# washberry.net
KiCad netlist of a schematic drawn in EAGLE
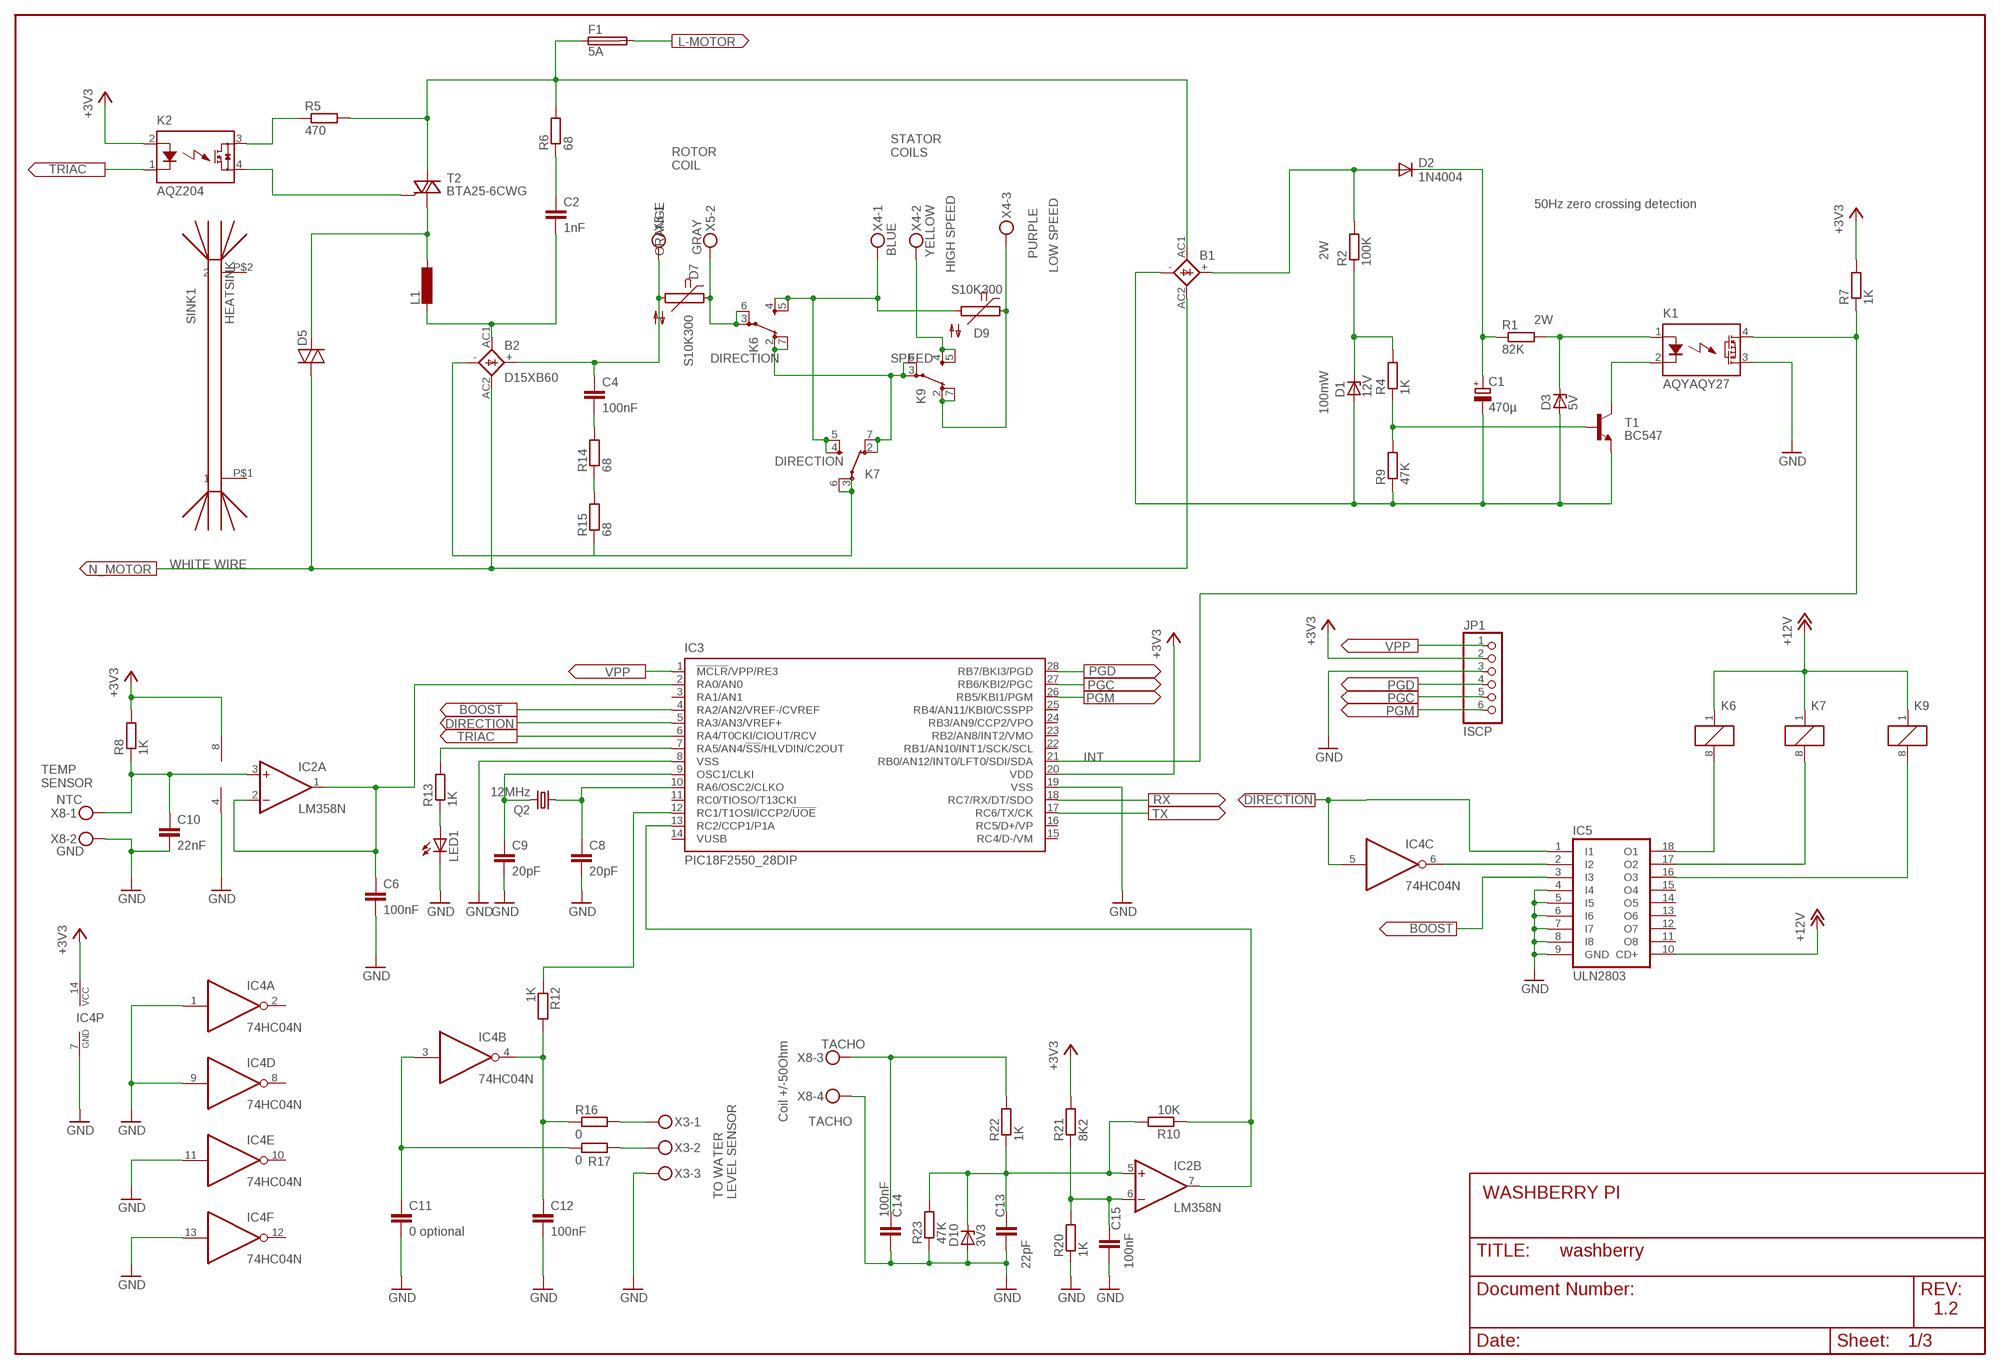
[diagram p0: schematic, sheet 1]
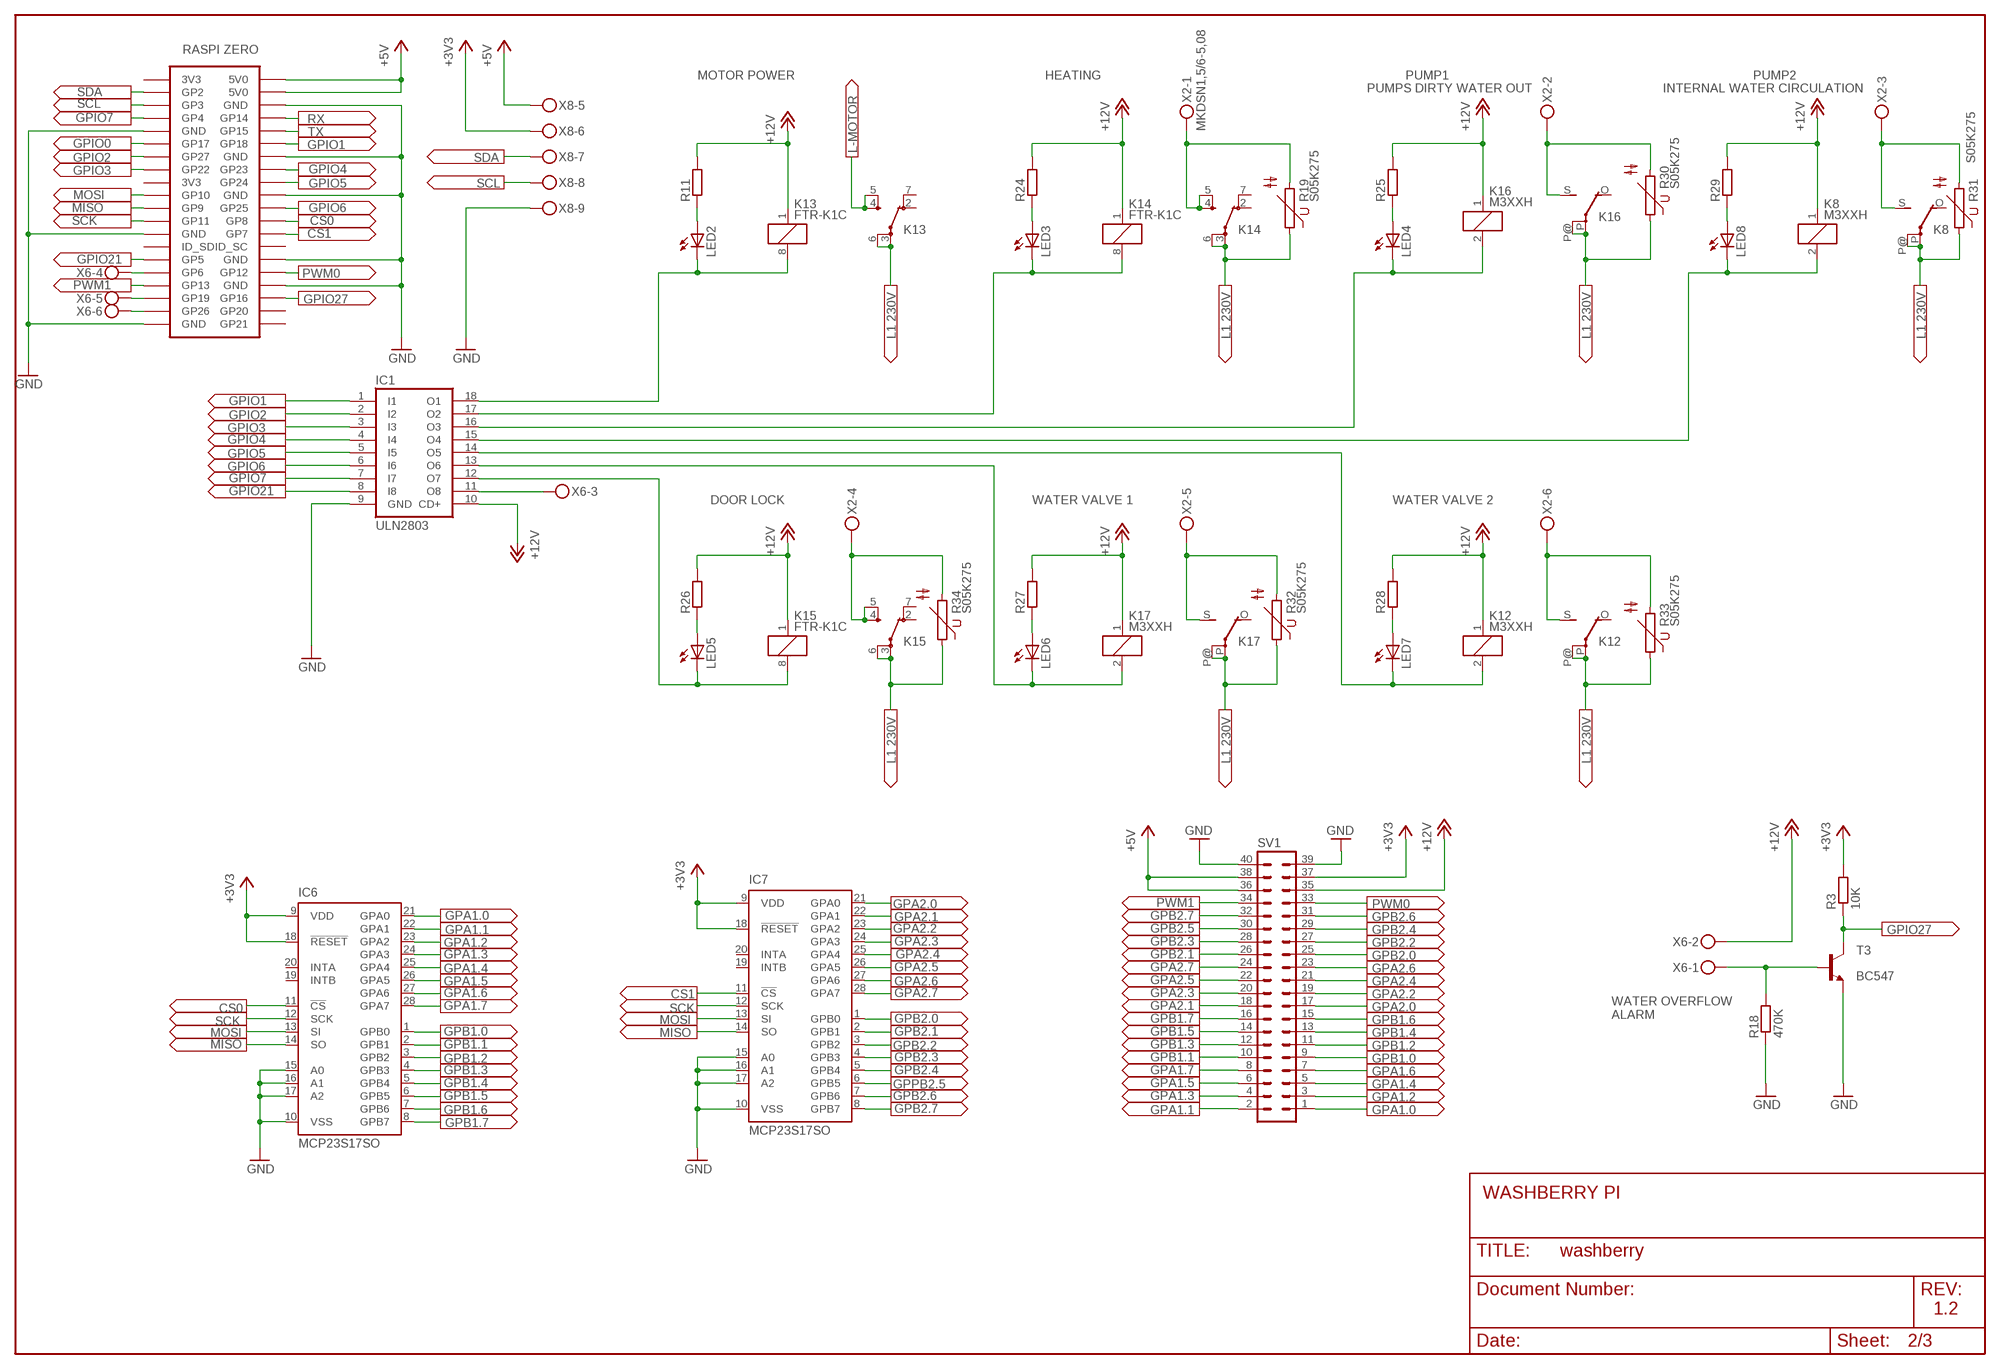
[diagram p1: schematic, sheet 2]
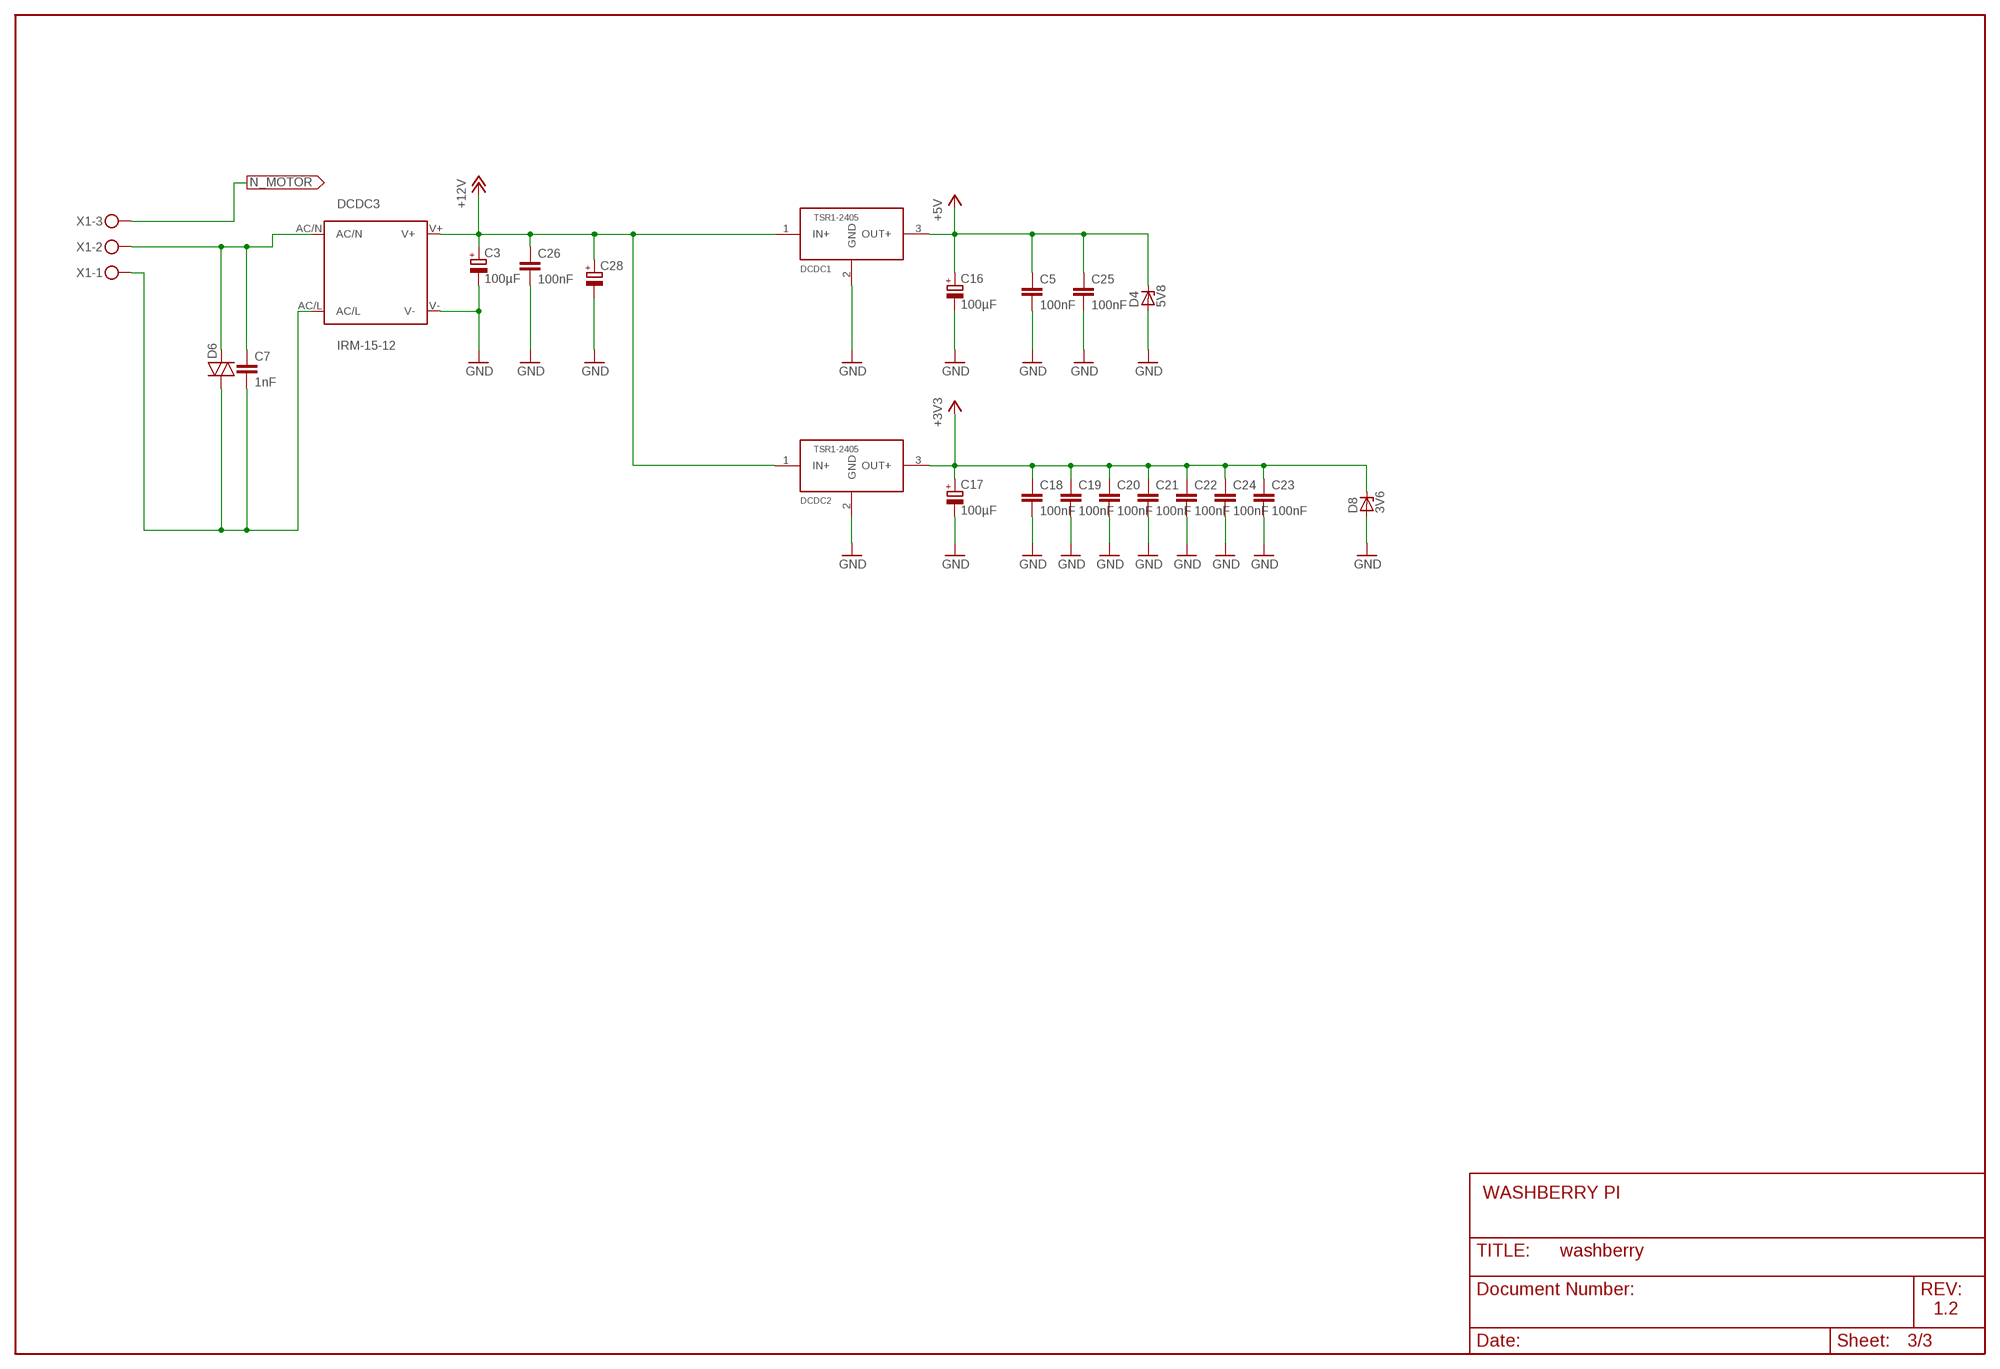
[diagram p2: schematic, sheet 3]

(export (version "E")
  (design (tool "Eeschema 10.0.6"))
  (components
    (comp (ref "IC1")
      (value "ULN2803")
      (footprint "eagle-import:DIL18")
      (libsource (lib "eagle-import") (part "ULN2803A"))
    )
    (comp (ref "IC6")
      (value "MCP23S17SO")
      (footprint "eagle-import:SO28W")
      (fields (field (name "MF") "MICROCHIP") (field (name "MPN") "MCP23S17-E/SO"))
      (libsource (lib "eagle-import") (part "MCP23S17SO"))
    )
    (comp (ref "IC7")
      (value "MCP23S17SO")
      (footprint "eagle-import:SO28W")
      (fields (field (name "MF") "MICROCHIP") (field (name "MPN") "MCP23S17-E/SO"))
      (libsource (lib "eagle-import") (part "MCP23S17SO"))
    )
    (comp (ref "K8")
      (value "M3XXH")
      (footprint "eagle-import:M3XXH")
      (libsource (lib "eagle-import") (part "M3XXH"))
    )
    (comp (ref "K12")
      (value "M3XXH")
      (footprint "eagle-import:M3XXH")
      (libsource (lib "eagle-import") (part "M3XXH"))
    )
    (comp (ref "K13")
      (value "FTR-K1C")
      (footprint "eagle-import:FTR-K1C")
      (libsource (lib "eagle-import") (part "FTR-K1C"))
    )
    (comp (ref "K14")
      (value "FTR-K1C")
      (footprint "eagle-import:FTR-K1C")
      (libsource (lib "eagle-import") (part "FTR-K1C"))
    )
    (comp (ref "K15")
      (value "FTR-K1C")
      (footprint "eagle-import:FTR-K1C")
      (libsource (lib "eagle-import") (part "FTR-K1C"))
    )
    (comp (ref "K16")
      (value "M3XXH")
      (footprint "eagle-import:M3XXH")
      (libsource (lib "eagle-import") (part "M3XXH"))
    )
    (comp (ref "K17")
      (value "M3XXH")
      (footprint "eagle-import:M3XXH")
      (libsource (lib "eagle-import") (part "M3XXH"))
    )
    (comp (ref "LED2")
      (value "LEDSML0805")
      (footprint "eagle-import:SML0805")
      (libsource (lib "eagle-import") (part "LEDSML0805"))
    )
    (comp (ref "LED3")
      (value "LEDSML0805")
      (footprint "eagle-import:SML0805")
      (libsource (lib "eagle-import") (part "LEDSML0805"))
    )
    (comp (ref "LED4")
      (value "LEDSML0805")
      (footprint "eagle-import:SML0805")
      (libsource (lib "eagle-import") (part "LEDSML0805"))
    )
    (comp (ref "LED5")
      (value "LEDSML0805")
      (footprint "eagle-import:SML0805")
      (libsource (lib "eagle-import") (part "LEDSML0805"))
    )
    (comp (ref "LED6")
      (value "LEDSML0805")
      (footprint "eagle-import:SML0805")
      (libsource (lib "eagle-import") (part "LEDSML0805"))
    )
    (comp (ref "LED7")
      (value "LEDSML0805")
      (footprint "eagle-import:SML0805")
      (libsource (lib "eagle-import") (part "LEDSML0805"))
    )
    (comp (ref "LED8")
      (value "LEDSML0805")
      (footprint "eagle-import:SML0805")
      (libsource (lib "eagle-import") (part "LEDSML0805"))
    )
    (comp (ref "R3")
      (value "10K")
      (footprint "eagle-import:0207_2V")
      (libsource (lib "eagle-import") (part "R-EU_0207/2V"))
    )
    (comp (ref "R11")
      (value "R-EU_R0805")
      (footprint "eagle-import:R0805")
      (libsource (lib "eagle-import") (part "R-EU_R0805"))
    )
    (comp (ref "R18")
      (value "470K")
      (footprint "eagle-import:0207_2V")
      (libsource (lib "eagle-import") (part "R-EU_0207/2V"))
    )
    (comp (ref "R19")
      (value "S05K275")
      (footprint "eagle-import:S05K275")
      (libsource (lib "eagle-import") (part "S05K275"))
    )
    (comp (ref "R24")
      (value "R-EU_R0805")
      (footprint "eagle-import:R0805")
      (libsource (lib "eagle-import") (part "R-EU_R0805"))
    )
    (comp (ref "R25")
      (value "R-EU_R0805")
      (footprint "eagle-import:R0805")
      (libsource (lib "eagle-import") (part "R-EU_R0805"))
    )
    (comp (ref "R26")
      (value "R-EU_R0805")
      (footprint "eagle-import:R0805")
      (libsource (lib "eagle-import") (part "R-EU_R0805"))
    )
    (comp (ref "R27")
      (value "R-EU_R0805")
      (footprint "eagle-import:R0805")
      (libsource (lib "eagle-import") (part "R-EU_R0805"))
    )
    (comp (ref "R28")
      (value "R-EU_R0805")
      (footprint "eagle-import:R0805")
      (libsource (lib "eagle-import") (part "R-EU_R0805"))
    )
    (comp (ref "R29")
      (value "R-EU_R0805")
      (footprint "eagle-import:R0805")
      (libsource (lib "eagle-import") (part "R-EU_R0805"))
    )
    (comp (ref "R30")
      (value "S05K275")
      (footprint "eagle-import:S05K275")
      (libsource (lib "eagle-import") (part "S05K275"))
    )
    (comp (ref "R31")
      (value "S05K275")
      (footprint "eagle-import:S05K275")
      (libsource (lib "eagle-import") (part "S05K275"))
    )
    (comp (ref "R32")
      (value "S05K275")
      (footprint "eagle-import:S05K275")
      (libsource (lib "eagle-import") (part "S05K275"))
    )
    (comp (ref "R33")
      (value "S05K275")
      (footprint "eagle-import:S05K275")
      (libsource (lib "eagle-import") (part "S05K275"))
    )
    (comp (ref "R34")
      (value "S05K275")
      (footprint "eagle-import:S05K275")
      (libsource (lib "eagle-import") (part "S05K275"))
    )
    (comp (ref "SV1")
      (value "ML40")
      (footprint "eagle-import:ML40")
      (libsource (lib "eagle-import") (part "ML40"))
    )
    (comp (ref "T3")
      (value "BC547")
      (footprint "eagle-import:TO92")
      (libsource (lib "eagle-import") (part "BC547"))
    )
    (comp (ref "U$3")
      (value "ZERO")
      (footprint "eagle-import:ZERO_NO_DIMENSION")
      (libsource (lib "eagle-import") (part "ZERO"))
    )
    (comp (ref "X2")
      (value "MKDSN1,5/6-5,08")
      (footprint "eagle-import:MKDSN1,5_6-5,08")
      (fields (field (name "MPN") "SMKDSN1,5/6-5,08"))
      (libsource (lib "eagle-import") (part "MKDSN1,5/6-5,08"))
    )
    (comp (ref "X6")
      (value "MKDSN1,5/6-5,08")
      (footprint "eagle-import:MKDSN1,5_6-5,08")
      (fields (field (name "MPN") "SMKDSN1,5/6-5,08"))
      (libsource (lib "eagle-import") (part "MKDSN1,5/6-5,08"))
    )
    (comp (ref "X8")
      (value "MKDSN1,5/9-5,08")
      (footprint "eagle-import:MKDSN1,5_9-5,08")
      (fields (field (name "MPN") "SMKDSN1,5/9-5,08"))
      (libsource (lib "eagle-import") (part "MKDSN1,5/9-5,08"))
    )
    (comp (ref "B1")
      (value "2KBB")
      (footprint "eagle-import:2KBB")
      (libsource (lib "eagle-import") (part "2KBB"))
    )
    (comp (ref "B2")
      (value "D15XB60")
      (footprint "eagle-import:5S")
      (libsource (lib "eagle-import") (part "D15XB60"))
    )
    (comp (ref "C1")
      (value "470µ")
      (footprint "eagle-import:E5-13")
      (libsource (lib "eagle-import") (part "CPOL-EUE5-13"))
    )
    (comp (ref "C2")
      (value "1nF")
      (footprint "eagle-import:C150-054X183")
      (libsource (lib "eagle-import") (part "C-EU150-054X183"))
    )
    (comp (ref "C4")
      (value "100nF")
      (footprint "eagle-import:C150-054X183")
      (libsource (lib "eagle-import") (part "C-EU150-054X183"))
    )
    (comp (ref "C6")
      (value "100nF")
      (footprint "eagle-import:C025-024X044")
      (libsource (lib "eagle-import") (part "C-EU025-024X044"))
    )
    (comp (ref "C8")
      (value "20pF")
      (footprint "eagle-import:C025-024X044")
      (libsource (lib "eagle-import") (part "C-EU025-024X044"))
    )
    (comp (ref "C9")
      (value "20pF")
      (footprint "eagle-import:C025-024X044")
      (libsource (lib "eagle-import") (part "C-EU025-024X044"))
    )
    (comp (ref "C10")
      (value "22nF")
      (footprint "eagle-import:C025-024X044")
      (libsource (lib "eagle-import") (part "C-EU025-024X044"))
    )
    (comp (ref "C11")
      (value "0 optional")
      (footprint "eagle-import:C025-024X044")
      (libsource (lib "eagle-import") (part "C-EU025-024X044"))
    )
    (comp (ref "C12")
      (value "100nF")
      (footprint "eagle-import:C025-024X044")
      (libsource (lib "eagle-import") (part "C-EU025-024X044"))
    )
    (comp (ref "C13")
      (value "22pF")
      (footprint "eagle-import:C025-024X044")
      (libsource (lib "eagle-import") (part "C-EU025-024X044"))
    )
    (comp (ref "C14")
      (value "100nF")
      (footprint "eagle-import:C025-024X044")
      (libsource (lib "eagle-import") (part "C-EU025-024X044"))
    )
    (comp (ref "C15")
      (value "100nF")
      (footprint "eagle-import:C025-024X044")
      (libsource (lib "eagle-import") (part "C-EU025-024X044"))
    )
    (comp (ref "D1")
      (value "12V")
      (footprint "eagle-import:DO34Z7")
      (libsource (lib "eagle-import") (part "ZENER-DIODEDO34-7"))
    )
    (comp (ref "D2")
      (value "1N4004")
      (footprint "eagle-import:DO41-10")
      (libsource (lib "eagle-import") (part "1N4004"))
    )
    (comp (ref "D3")
      (value "5V")
      (footprint "eagle-import:DO34Z7")
      (libsource (lib "eagle-import") (part "ZENER-DIODEDO34-7"))
    )
    (comp (ref "D5")
      (value "DIAC-DO35-10")
      (footprint "eagle-import:DO35-10")
      (libsource (lib "eagle-import") (part "DIAC-DO35-10"))
    )
    (comp (ref "D7")
      (value "S10K300")
      (footprint "eagle-import:S10K300")
      (libsource (lib "eagle-import") (part "S10K300"))
    )
    (comp (ref "D9")
      (value "S10K300")
      (footprint "eagle-import:S10K300")
      (libsource (lib "eagle-import") (part "S10K300"))
    )
    (comp (ref "D10")
      (value "3V3")
      (footprint "eagle-import:DO34Z7")
      (libsource (lib "eagle-import") (part "ZENER-DIODEDO34-7"))
    )
    (comp (ref "F1")
      (value "5A")
      (footprint "eagle-import:GSH15")
      (fields (field (name "MPN") "64900001039"))
      (libsource (lib "eagle-import") (part "GSH15"))
    )
    (comp (ref "IC2")
      (value "LM358N")
      (footprint "eagle-import:DIL08")
      (libsource (lib "eagle-import") (part "LM358N"))
    )
    (comp (ref "IC3")
      (value "PIC18F2550_28DIP")
      (footprint "eagle-import:DIL28-3")
      (fields (field (name "MF") "MICROCHIP") (field (name "MPN") "PIC18F2550-I/SP"))
      (libsource (lib "eagle-import") (part "PIC18F2_28DIP550"))
    )
    (comp (ref "IC4")
      (value "74HC04N")
      (footprint "eagle-import:DIL14")
      (libsource (lib "eagle-import") (part "7404NHC"))
    )
    (comp (ref "IC5")
      (value "ULN2803")
      (footprint "eagle-import:DIL18")
      (libsource (lib "eagle-import") (part "ULN2803A"))
    )
    (comp (ref "JP1")
      (value "ISCP")
      (footprint "eagle-import:1X06")
      (libsource (lib "eagle-import") (part "PINHD-1X6"))
    )
    (comp (ref "K1")
      (value "AQYAQY27")
      (footprint "eagle-import:AQY27")
      (libsource (lib "eagle-import") (part "AQYAQY27"))
    )
    (comp (ref "K2")
      (value "AQZ204")
      (footprint "eagle-import:AQZ-SIL04")
      (libsource (lib "eagle-import") (part "AQZ204"))
    )
    (comp (ref "K6")
      (value "FTR-K1C")
      (footprint "eagle-import:FTR-K1C")
      (libsource (lib "eagle-import") (part "FTR-K1C"))
    )
    (comp (ref "K7")
      (value "FTR-K1C")
      (footprint "eagle-import:FTR-K1C")
      (libsource (lib "eagle-import") (part "FTR-K1C"))
    )
    (comp (ref "K9")
      (value "FTR-K1C")
      (footprint "eagle-import:FTR-K1C")
      (libsource (lib "eagle-import") (part "FTR-K1C"))
    )
    (comp (ref "L1")
      (value "L-EUTJ5-U1")
      (footprint "eagle-import:TJ5-U1")
      (libsource (lib "eagle-import") (part "L-EUTJ5-U1"))
    )
    (comp (ref "LED1")
      (value "LEDCHIPLED_0805")
      (footprint "eagle-import:CHIPLED_0805")
      (libsource (lib "eagle-import") (part "LEDCHIPLED_0805"))
    )
    (comp (ref "Q2")
      (value "12MHz")
      (footprint "eagle-import:HC49_S")
      (libsource (lib "eagle-import") (part "CRYSTALHC49S"))
    )
    (comp (ref "R1")
      (value "82K")
      (footprint "eagle-import:0617_17")
      (libsource (lib "eagle-import") (part "R-EU_0617/17"))
    )
    (comp (ref "R2")
      (value "100K")
      (footprint "eagle-import:0617_17")
      (libsource (lib "eagle-import") (part "R-EU_0617/17"))
    )
    (comp (ref "R4")
      (value "1K")
      (footprint "eagle-import:0411V")
      (libsource (lib "eagle-import") (part "R-EU_0411/3V"))
    )
    (comp (ref "R5")
      (value "470")
      (footprint "eagle-import:P0613_15")
      (libsource (lib "eagle-import") (part "R-EU_0613/15"))
    )
    (comp (ref "R6")
      (value "68")
      (footprint "eagle-import:P0613_15")
      (libsource (lib "eagle-import") (part "R-EU_0613/15"))
    )
    (comp (ref "R7")
      (value "1K")
      (footprint "eagle-import:0411V")
      (libsource (lib "eagle-import") (part "R-EU_0411/3V"))
    )
    (comp (ref "R8")
      (value "1K")
      (footprint "eagle-import:0411V")
      (libsource (lib "eagle-import") (part "R-EU_0411/3V"))
    )
    (comp (ref "R9")
      (value "47K")
      (footprint "eagle-import:0411V")
      (libsource (lib "eagle-import") (part "R-EU_0411/3V"))
    )
    (comp (ref "R10")
      (value "10K")
      (footprint "eagle-import:0411V")
      (libsource (lib "eagle-import") (part "R-EU_0411/3V"))
    )
    (comp (ref "R12")
      (value "1K")
      (footprint "eagle-import:0411V")
      (libsource (lib "eagle-import") (part "R-EU_0411/3V"))
    )
    (comp (ref "R13")
      (value "1K")
      (footprint "eagle-import:R0805")
      (libsource (lib "eagle-import") (part "R-EU_R0805"))
    )
    (comp (ref "R14")
      (value "68")
      (footprint "eagle-import:0617_17")
      (libsource (lib "eagle-import") (part "R-EU_0617/17"))
    )
    (comp (ref "R15")
      (value "68")
      (footprint "eagle-import:0617_17")
      (libsource (lib "eagle-import") (part "R-EU_0617/17"))
    )
    (comp (ref "R16")
      (value "0")
      (footprint "eagle-import:0411V")
      (libsource (lib "eagle-import") (part "R-EU_0411/3V"))
    )
    (comp (ref "R17")
      (value "0")
      (footprint "eagle-import:0411V")
      (libsource (lib "eagle-import") (part "R-EU_0411/3V"))
    )
    (comp (ref "R20")
      (value "1K")
      (footprint "eagle-import:0411V")
      (libsource (lib "eagle-import") (part "R-EU_0411/3V"))
    )
    (comp (ref "R21")
      (value "8K2")
      (footprint "eagle-import:0411V")
      (libsource (lib "eagle-import") (part "R-EU_0411/3V"))
    )
    (comp (ref "R22")
      (value "1K")
      (footprint "eagle-import:0411V")
      (libsource (lib "eagle-import") (part "R-EU_0411/3V"))
    )
    (comp (ref "R23")
      (value "47K")
      (footprint "eagle-import:0411V")
      (libsource (lib "eagle-import") (part "R-EU_0411/3V"))
    )
    (comp (ref "SINK1")
      (value "HEATSINK")
      (footprint "eagle-import:W_HEATSINK")
      (libsource (lib "eagle-import") (part "W_HEATSINK"))
    )
    (comp (ref "T1")
      (value "BC547")
      (footprint "eagle-import:TO92")
      (libsource (lib "eagle-import") (part "BC547"))
    )
    (comp (ref "T2")
      (value "BTA25-6CWG")
      (footprint "eagle-import:TO220BV")
      (libsource (lib "eagle-import") (part "BT138-V"))
    )
    (comp (ref "X3")
      (value "MKDSN1,5/3-5,08")
      (footprint "eagle-import:MKDSN1,5_3-5,08")
      (fields (field (name "MPN") "SMKDSN1,5/3-5,08"))
      (libsource (lib "eagle-import") (part "MKDSN1,5/3-5,08"))
    )
    (comp (ref "X4")
      (value "MKDSN1,5/3-5,08")
      (footprint "eagle-import:MKDSN1,5_3-5,08")
      (fields (field (name "MPN") "SMKDSN1,5/3-5,08"))
      (libsource (lib "eagle-import") (part "MKDSN1,5/3-5,08"))
    )
    (comp (ref "X5")
      (value "MKDSN1,5/2-5,08")
      (footprint "eagle-import:MKDSN1,5_2-5,08")
      (fields (field (name "MPN") "MKDSN 1,5/2-5.08"))
      (libsource (lib "eagle-import") (part "MKDSN1,5/2-5,08"))
    )
    (comp (ref "C3")
      (value "100µF")
      (footprint "eagle-import:E3,5-8")
      (libsource (lib "eagle-import") (part "CPOL-EUE3.5-8"))
    )
    (comp (ref "C5")
      (value "100nF")
      (footprint "eagle-import:C025-024X044")
      (libsource (lib "eagle-import") (part "C-EU025-024X044"))
    )
    (comp (ref "C7")
      (value "1nF")
      (footprint "eagle-import:C150-091X182")
      (libsource (lib "eagle-import") (part "C-EU150-091X182"))
    )
    (comp (ref "C16")
      (value "100µF")
      (footprint "eagle-import:E3,5-8")
      (libsource (lib "eagle-import") (part "CPOL-EUE3.5-8"))
    )
    (comp (ref "C17")
      (value "100µF")
      (footprint "eagle-import:E2-5")
      (libsource (lib "eagle-import") (part "CPOL-EUE2-5"))
    )
    (comp (ref "C18")
      (value "100nF")
      (footprint "eagle-import:C025-024X044")
      (libsource (lib "eagle-import") (part "C-EU025-024X044"))
    )
    (comp (ref "C19")
      (value "100nF")
      (footprint "eagle-import:C025-024X044")
      (libsource (lib "eagle-import") (part "C-EU025-024X044"))
    )
    (comp (ref "C20")
      (value "100nF")
      (footprint "eagle-import:C025-024X044")
      (libsource (lib "eagle-import") (part "C-EU025-024X044"))
    )
    (comp (ref "C21")
      (value "100nF")
      (footprint "eagle-import:C025-024X044")
      (libsource (lib "eagle-import") (part "C-EU025-024X044"))
    )
    (comp (ref "C22")
      (value "100nF")
      (footprint "eagle-import:C025-024X044")
      (libsource (lib "eagle-import") (part "C-EU025-024X044"))
    )
    (comp (ref "C23")
      (value "100nF")
      (footprint "eagle-import:C025-024X044")
      (libsource (lib "eagle-import") (part "C-EU025-024X044"))
    )
    (comp (ref "C24")
      (value "100nF")
      (footprint "eagle-import:C025-024X044")
      (libsource (lib "eagle-import") (part "C-EU025-024X044"))
    )
    (comp (ref "C25")
      (value "100nF")
      (footprint "eagle-import:C025-024X044")
      (libsource (lib "eagle-import") (part "C-EU025-024X044"))
    )
    (comp (ref "C26")
      (value "100nF")
      (footprint "eagle-import:C025-024X044")
      (libsource (lib "eagle-import") (part "C-EU025-024X044"))
    )
    (comp (ref "C28")
      (value "CPOL-EUE2-5")
      (footprint "eagle-import:E2-5")
      (libsource (lib "eagle-import") (part "CPOL-EUE2-5"))
    )
    (comp (ref "D4")
      (value "5V8")
      (footprint "eagle-import:DO34Z7")
      (libsource (lib "eagle-import") (part "ZENER-DIODEDO34-7"))
    )
    (comp (ref "D6")
      (value "DIAC-DO35-10")
      (footprint "eagle-import:DO35-10")
      (libsource (lib "eagle-import") (part "DIAC-DO35-10"))
    )
    (comp (ref "D8")
      (value "3V6")
      (footprint "eagle-import:DO34Z7")
      (libsource (lib "eagle-import") (part "ZENER-DIODEDO34-7"))
    )
    (comp (ref "DCDC1")
      (value "TSR1-2405")
      (footprint "eagle-import:SIPTO220")
      (libsource (lib "eagle-import") (part "TSR1-24XX"))
    )
    (comp (ref "DCDC2")
      (value "TSR1-2405")
      (footprint "eagle-import:SIPTO220")
      (libsource (lib "eagle-import") (part "TSR1-24XX"))
    )
    (comp (ref "DCDC3")
      (value "IRM-15-12")
      (footprint "eagle-import:IRM_15_20")
      (libsource (lib "eagle-import") (part "IRM_15/20IRM_15/20"))
    )
    (comp (ref "X1")
      (value "MKDSN1,5/3-5,08")
      (footprint "eagle-import:MKDSN1,5_3-5,08")
      (fields (field (name "MPN") "SMKDSN1,5/3-5,08"))
      (libsource (lib "eagle-import") (part "MKDSN1,5/3-5,08"))
    )
  )
  (nets
    (net (code "1") (name "+3V3") (class "Default")
      (node (ref "C17") (pin "+") (pinfunction "+_+") (pintype "passive"))
      (node (ref "C18") (pin "1") (pinfunction "1_1") (pintype "passive"))
      (node (ref "C19") (pin "1") (pinfunction "1_1") (pintype "passive"))
      (node (ref "C20") (pin "1") (pinfunction "1_1") (pintype "passive"))
      (node (ref "C21") (pin "1") (pinfunction "1_1") (pintype "passive"))
      (node (ref "C22") (pin "1") (pinfunction "1_1") (pintype "passive"))
      (node (ref "C23") (pin "1") (pinfunction "1_1") (pintype "passive"))
      (node (ref "C24") (pin "1") (pinfunction "1_1") (pintype "passive"))
      (node (ref "D8") (pin "C") (pinfunction "C_C") (pintype "passive"))
      (node (ref "DCDC2") (pin "3") (pinfunction "OUT+_3") (pintype "output"))
      (node (ref "IC2") (pin "8") (pinfunction "V+_8") (pintype "power_in"))
      (node (ref "IC3") (pin "20") (pinfunction "VDD_20") (pintype "power_in"))
      (node (ref "IC4") (pin "14") (pinfunction "VCC_14") (pintype "power_in"))
      (node (ref "IC6") (pin "18") (pinfunction "~{RESET}_18") (pintype "input"))
      (node (ref "IC6") (pin "9") (pinfunction "VDD_9") (pintype "power_in"))
      (node (ref "IC7") (pin "18") (pinfunction "~{RESET}_18") (pintype "input"))
      (node (ref "IC7") (pin "9") (pinfunction "VDD_9") (pintype "power_in"))
      (node (ref "JP1") (pin "2") (pinfunction "2_2") (pintype "passive"))
      (node (ref "K2") (pin "2") (pinfunction "A_2") (pintype "passive"))
      (node (ref "R21") (pin "2") (pinfunction "2_2") (pintype "passive"))
      (node (ref "R3") (pin "2") (pinfunction "2_2") (pintype "passive"))
      (node (ref "R7") (pin "2") (pinfunction "2_2") (pintype "passive"))
      (node (ref "R8") (pin "2") (pinfunction "2_2") (pintype "passive"))
      (node (ref "SV1") (pin "37") (pinfunction "37_37") (pintype "passive"))
      (node (ref "X8") (pin "6") (pinfunction "KL_6") (pintype "passive"))
    )
    (net (code "2") (name "+5V") (class "Default")
      (node (ref "C16") (pin "+") (pinfunction "+_+") (pintype "passive"))
      (node (ref "C25") (pin "1") (pinfunction "1_1") (pintype "passive"))
      (node (ref "C5") (pin "1") (pinfunction "1_1") (pintype "passive"))
      (node (ref "D4") (pin "C") (pinfunction "C_C") (pintype "passive"))
      (node (ref "DCDC1") (pin "3") (pinfunction "OUT+_3") (pintype "output"))
      (node (ref "SV1") (pin "36") (pinfunction "36_36") (pintype "passive"))
      (node (ref "SV1") (pin "38") (pinfunction "38_38") (pintype "passive"))
      (node (ref "U$3") (pin "2") (pinfunction "5V0_2") (pintype "bidirectional"))
      (node (ref "U$3") (pin "4") (pinfunction "5V0_4") (pintype "bidirectional"))
      (node (ref "X8") (pin "5") (pinfunction "KL_5") (pintype "passive"))
    )
    (net (code "3") (name "+12V") (class "Default")
      (node (ref "C26") (pin "1") (pinfunction "1_1") (pintype "passive"))
      (node (ref "C28") (pin "+") (pinfunction "+_+") (pintype "passive"))
      (node (ref "C3") (pin "+") (pinfunction "+_+") (pintype "passive"))
      (node (ref "DCDC1") (pin "1") (pinfunction "IN+_1") (pintype "bidirectional"))
      (node (ref "DCDC2") (pin "1") (pinfunction "IN+_1") (pintype "bidirectional"))
      (node (ref "DCDC3") (pin "V+") (pinfunction "V+_V+") (pintype "output"))
      (node (ref "IC1") (pin "10") (pinfunction "CD+_10") (pintype "passive"))
      (node (ref "IC5") (pin "10") (pinfunction "CD+_10") (pintype "passive"))
      (node (ref "K12") (pin "1") (pinfunction "1_1") (pintype "passive"))
      (node (ref "K13") (pin "1") (pinfunction "1_1") (pintype "passive"))
      (node (ref "K14") (pin "1") (pinfunction "1_1") (pintype "passive"))
      (node (ref "K15") (pin "1") (pinfunction "1_1") (pintype "passive"))
      (node (ref "K16") (pin "1") (pinfunction "1_1") (pintype "passive"))
      (node (ref "K17") (pin "1") (pinfunction "1_1") (pintype "passive"))
      (node (ref "K6") (pin "1") (pinfunction "1_1") (pintype "passive"))
      (node (ref "K7") (pin "1") (pinfunction "1_1") (pintype "passive"))
      (node (ref "K8") (pin "1") (pinfunction "1_1") (pintype "passive"))
      (node (ref "K9") (pin "1") (pinfunction "1_1") (pintype "passive"))
      (node (ref "R11") (pin "2") (pinfunction "2_2") (pintype "passive"))
      (node (ref "R24") (pin "2") (pinfunction "2_2") (pintype "passive"))
      (node (ref "R25") (pin "2") (pinfunction "2_2") (pintype "passive"))
      (node (ref "R26") (pin "2") (pinfunction "2_2") (pintype "passive"))
      (node (ref "R27") (pin "2") (pinfunction "2_2") (pintype "passive"))
      (node (ref "R28") (pin "2") (pinfunction "2_2") (pintype "passive"))
      (node (ref "R29") (pin "2") (pinfunction "2_2") (pintype "passive"))
      (node (ref "SV1") (pin "35") (pinfunction "35_35") (pintype "passive"))
      (node (ref "X6") (pin "2") (pinfunction "KL_2") (pintype "passive"))
    )
    (net (code "4") (name "BOOST") (class "Default")
      (node (ref "IC3") (pin "4") (pinfunction "RA2/AN2/VREF-/CVREF_4") (pintype "bidirectional"))
      (node (ref "IC5") (pin "3") (pinfunction "I3_3") (pintype "input"))
    )
    (net (code "5") (name "CS0") (class "Default")
      (node (ref "IC6") (pin "11") (pinfunction "~{CS}_11") (pintype "input"))
      (node (ref "U$3") (pin "24") (pinfunction "GP8_24") (pintype "bidirectional"))
    )
    (net (code "6") (name "CS1") (class "Default")
      (node (ref "IC7") (pin "11") (pinfunction "~{CS}_11") (pintype "input"))
      (node (ref "U$3") (pin "26") (pinfunction "GP7_26") (pintype "bidirectional"))
    )
    (net (code "7") (name "DIRECTION") (class "Default")
      (node (ref "IC3") (pin "5") (pinfunction "RA3/AN3/VREF+_5") (pintype "bidirectional"))
      (node (ref "IC4") (pin "5") (pinfunction "I_5") (pintype "input"))
      (node (ref "IC5") (pin "1") (pinfunction "I1_1") (pintype "input"))
    )
    (net (code "8") (name "GND") (class "Default")
      (node (ref "C10") (pin "2") (pinfunction "2_2") (pintype "passive"))
      (node (ref "C11") (pin "2") (pinfunction "2_2") (pintype "passive"))
      (node (ref "C12") (pin "2") (pinfunction "2_2") (pintype "passive"))
      (node (ref "C13") (pin "2") (pinfunction "2_2") (pintype "passive"))
      (node (ref "C14") (pin "2") (pinfunction "2_2") (pintype "passive"))
      (node (ref "C15") (pin "2") (pinfunction "2_2") (pintype "passive"))
      (node (ref "C16") (pin "-") (pinfunction "-_-") (pintype "passive"))
      (node (ref "C17") (pin "-") (pinfunction "-_-") (pintype "passive"))
      (node (ref "C18") (pin "2") (pinfunction "2_2") (pintype "passive"))
      (node (ref "C19") (pin "2") (pinfunction "2_2") (pintype "passive"))
      (node (ref "C20") (pin "2") (pinfunction "2_2") (pintype "passive"))
      (node (ref "C21") (pin "2") (pinfunction "2_2") (pintype "passive"))
      (node (ref "C22") (pin "2") (pinfunction "2_2") (pintype "passive"))
      (node (ref "C23") (pin "2") (pinfunction "2_2") (pintype "passive"))
      (node (ref "C24") (pin "2") (pinfunction "2_2") (pintype "passive"))
      (node (ref "C25") (pin "2") (pinfunction "2_2") (pintype "passive"))
      (node (ref "C26") (pin "2") (pinfunction "2_2") (pintype "passive"))
      (node (ref "C28") (pin "-") (pinfunction "-_-") (pintype "passive"))
      (node (ref "C3") (pin "-") (pinfunction "-_-") (pintype "passive"))
      (node (ref "C5") (pin "2") (pinfunction "2_2") (pintype "passive"))
      (node (ref "C6") (pin "2") (pinfunction "2_2") (pintype "passive"))
      (node (ref "C8") (pin "2") (pinfunction "2_2") (pintype "passive"))
      (node (ref "C9") (pin "2") (pinfunction "2_2") (pintype "passive"))
      (node (ref "D10") (pin "A") (pinfunction "A_A") (pintype "passive"))
      (node (ref "D4") (pin "A") (pinfunction "A_A") (pintype "passive"))
      (node (ref "D8") (pin "A") (pinfunction "A_A") (pintype "passive"))
      (node (ref "DCDC1") (pin "2") (pinfunction "GND_2") (pintype "bidirectional"))
      (node (ref "DCDC2") (pin "2") (pinfunction "GND_2") (pintype "bidirectional"))
      (node (ref "DCDC3") (pin "V-") (pinfunction "V-_V-") (pintype "output"))
      (node (ref "IC1") (pin "9") (pinfunction "GND_9") (pintype "power_in"))
      (node (ref "IC2") (pin "4") (pinfunction "V-_4") (pintype "power_in"))
      (node (ref "IC3") (pin "19") (pinfunction "VSS_19") (pintype "power_in"))
      (node (ref "IC3") (pin "8") (pinfunction "VSS_8") (pintype "power_in"))
      (node (ref "IC4") (pin "1") (pinfunction "I_1") (pintype "input"))
      (node (ref "IC4") (pin "11") (pinfunction "I_11") (pintype "input"))
      (node (ref "IC4") (pin "13") (pinfunction "I_13") (pintype "input"))
      (node (ref "IC4") (pin "7") (pinfunction "GND_7") (pintype "power_in"))
      (node (ref "IC4") (pin "9") (pinfunction "I_9") (pintype "input"))
      (node (ref "IC5") (pin "4") (pinfunction "I4_4") (pintype "input"))
      (node (ref "IC5") (pin "5") (pinfunction "I5_5") (pintype "input"))
      (node (ref "IC5") (pin "6") (pinfunction "I6_6") (pintype "input"))
      (node (ref "IC5") (pin "7") (pinfunction "I7_7") (pintype "input"))
      (node (ref "IC5") (pin "8") (pinfunction "I8_8") (pintype "input"))
      (node (ref "IC5") (pin "9") (pinfunction "GND_9") (pintype "power_in"))
      (node (ref "IC6") (pin "10") (pinfunction "VSS_10") (pintype "power_in"))
      (node (ref "IC6") (pin "15") (pinfunction "A0_15") (pintype "input"))
      (node (ref "IC6") (pin "16") (pinfunction "A1_16") (pintype "input"))
      (node (ref "IC6") (pin "17") (pinfunction "A2_17") (pintype "input"))
      (node (ref "IC7") (pin "10") (pinfunction "VSS_10") (pintype "power_in"))
      (node (ref "IC7") (pin "15") (pinfunction "A0_15") (pintype "input"))
      (node (ref "IC7") (pin "16") (pinfunction "A1_16") (pintype "input"))
      (node (ref "IC7") (pin "17") (pinfunction "A2_17") (pintype "input"))
      (node (ref "JP1") (pin "3") (pinfunction "3_3") (pintype "passive"))
      (node (ref "K1") (pin "3") (pinfunction "DS2_3") (pintype "passive"))
      (node (ref "LED1") (pin "C") (pinfunction "C_C") (pintype "passive"))
      (node (ref "R18") (pin "1") (pinfunction "1_1") (pintype "passive"))
      (node (ref "R20") (pin "1") (pinfunction "1_1") (pintype "passive"))
      (node (ref "R23") (pin "1") (pinfunction "1_1") (pintype "passive"))
      (node (ref "SV1") (pin "39") (pinfunction "39_39") (pintype "passive"))
      (node (ref "SV1") (pin "40") (pinfunction "40_40") (pintype "passive"))
      (node (ref "T3") (pin "1") (pinfunction "E_1") (pintype "passive"))
      (node (ref "U$3") (pin "14") (pinfunction "GND_14") (pintype "bidirectional"))
      (node (ref "U$3") (pin "20") (pinfunction "GND_20") (pintype "bidirectional"))
      (node (ref "U$3") (pin "25") (pinfunction "GND_25") (pintype "bidirectional"))
      (node (ref "U$3") (pin "30") (pinfunction "GND_30") (pintype "bidirectional"))
      (node (ref "U$3") (pin "34") (pinfunction "GND_34") (pintype "bidirectional"))
      (node (ref "U$3") (pin "39") (pinfunction "GND_39") (pintype "bidirectional"))
      (node (ref "U$3") (pin "6") (pinfunction "GND_6") (pintype "bidirectional"))
      (node (ref "U$3") (pin "9") (pinfunction "GND_9") (pintype "bidirectional"))
      (node (ref "X3") (pin "3") (pinfunction "KL_3") (pintype "passive"))
      (node (ref "X8") (pin "2") (pinfunction "KL_2") (pintype "passive"))
      (node (ref "X8") (pin "4") (pinfunction "KL_4") (pintype "passive"))
      (node (ref "X8") (pin "9") (pinfunction "KL_9") (pintype "passive"))
    )
    (net (code "9") (name "GPA1.0") (class "Default")
      (node (ref "IC6") (pin "21") (pinfunction "GPA0_21") (pintype "bidirectional"))
      (node (ref "SV1") (pin "1") (pinfunction "1_1") (pintype "passive"))
    )
    (net (code "10") (name "GPA1.1") (class "Default")
      (node (ref "IC6") (pin "22") (pinfunction "GPA1_22") (pintype "bidirectional"))
      (node (ref "SV1") (pin "2") (pinfunction "2_2") (pintype "passive"))
    )
    (net (code "11") (name "GPA1.2") (class "Default")
      (node (ref "IC6") (pin "23") (pinfunction "GPA2_23") (pintype "bidirectional"))
      (node (ref "SV1") (pin "3") (pinfunction "3_3") (pintype "passive"))
    )
    (net (code "12") (name "GPA1.3") (class "Default")
      (node (ref "IC6") (pin "24") (pinfunction "GPA3_24") (pintype "bidirectional"))
      (node (ref "SV1") (pin "4") (pinfunction "4_4") (pintype "passive"))
    )
    (net (code "13") (name "GPA1.4") (class "Default")
      (node (ref "IC6") (pin "25") (pinfunction "GPA4_25") (pintype "bidirectional"))
      (node (ref "SV1") (pin "5") (pinfunction "5_5") (pintype "passive"))
    )
    (net (code "14") (name "GPA1.5") (class "Default")
      (node (ref "IC6") (pin "26") (pinfunction "GPA5_26") (pintype "bidirectional"))
      (node (ref "SV1") (pin "6") (pinfunction "6_6") (pintype "passive"))
    )
    (net (code "15") (name "GPA1.6") (class "Default")
      (node (ref "IC6") (pin "27") (pinfunction "GPA6_27") (pintype "bidirectional"))
      (node (ref "SV1") (pin "7") (pinfunction "7_7") (pintype "passive"))
    )
    (net (code "16") (name "GPA1.7") (class "Default")
      (node (ref "IC6") (pin "28") (pinfunction "GPA7_28") (pintype "bidirectional"))
      (node (ref "SV1") (pin "8") (pinfunction "8_8") (pintype "passive"))
    )
    (net (code "17") (name "GPA2.0") (class "Default")
      (node (ref "IC7") (pin "21") (pinfunction "GPA0_21") (pintype "bidirectional"))
      (node (ref "SV1") (pin "17") (pinfunction "17_17") (pintype "passive"))
    )
    (net (code "18") (name "GPA2.1") (class "Default")
      (node (ref "IC7") (pin "22") (pinfunction "GPA1_22") (pintype "bidirectional"))
      (node (ref "SV1") (pin "18") (pinfunction "18_18") (pintype "passive"))
    )
    (net (code "19") (name "GPA2.2") (class "Default")
      (node (ref "IC7") (pin "23") (pinfunction "GPA2_23") (pintype "bidirectional"))
      (node (ref "SV1") (pin "19") (pinfunction "19_19") (pintype "passive"))
    )
    (net (code "20") (name "GPA2.3") (class "Default")
      (node (ref "IC7") (pin "24") (pinfunction "GPA3_24") (pintype "bidirectional"))
      (node (ref "SV1") (pin "20") (pinfunction "20_20") (pintype "passive"))
    )
    (net (code "21") (name "GPA2.4") (class "Default")
      (node (ref "IC7") (pin "25") (pinfunction "GPA4_25") (pintype "bidirectional"))
      (node (ref "SV1") (pin "21") (pinfunction "21_21") (pintype "passive"))
    )
    (net (code "22") (name "GPA2.5") (class "Default")
      (node (ref "IC7") (pin "26") (pinfunction "GPA5_26") (pintype "bidirectional"))
      (node (ref "SV1") (pin "22") (pinfunction "22_22") (pintype "passive"))
    )
    (net (code "23") (name "GPA2.6") (class "Default")
      (node (ref "IC7") (pin "27") (pinfunction "GPA6_27") (pintype "bidirectional"))
      (node (ref "SV1") (pin "23") (pinfunction "23_23") (pintype "passive"))
    )
    (net (code "24") (name "GPA2.7") (class "Default")
      (node (ref "IC7") (pin "28") (pinfunction "GPA7_28") (pintype "bidirectional"))
      (node (ref "SV1") (pin "24") (pinfunction "24_24") (pintype "passive"))
    )
    (net (code "25") (name "GPB1.0") (class "Default")
      (node (ref "IC6") (pin "1") (pinfunction "GPB0_1") (pintype "bidirectional"))
      (node (ref "SV1") (pin "9") (pinfunction "9_9") (pintype "passive"))
    )
    (net (code "26") (name "GPB1.1") (class "Default")
      (node (ref "IC6") (pin "2") (pinfunction "GPB1_2") (pintype "bidirectional"))
      (node (ref "SV1") (pin "10") (pinfunction "10_10") (pintype "passive"))
    )
    (net (code "27") (name "GPB1.2") (class "Default")
      (node (ref "IC6") (pin "3") (pinfunction "GPB2_3") (pintype "bidirectional"))
      (node (ref "SV1") (pin "11") (pinfunction "11_11") (pintype "passive"))
    )
    (net (code "28") (name "GPB1.3") (class "Default")
      (node (ref "IC6") (pin "4") (pinfunction "GPB3_4") (pintype "bidirectional"))
      (node (ref "SV1") (pin "12") (pinfunction "12_12") (pintype "passive"))
    )
    (net (code "29") (name "GPB1.4") (class "Default")
      (node (ref "IC6") (pin "5") (pinfunction "GPB4_5") (pintype "bidirectional"))
      (node (ref "SV1") (pin "13") (pinfunction "13_13") (pintype "passive"))
    )
    (net (code "30") (name "GPB1.5") (class "Default")
      (node (ref "IC6") (pin "6") (pinfunction "GPB5_6") (pintype "bidirectional"))
      (node (ref "SV1") (pin "14") (pinfunction "14_14") (pintype "passive"))
    )
    (net (code "31") (name "GPB1.6") (class "Default")
      (node (ref "IC6") (pin "7") (pinfunction "GPB6_7") (pintype "bidirectional"))
      (node (ref "SV1") (pin "15") (pinfunction "15_15") (pintype "passive"))
    )
    (net (code "32") (name "GPB1.7") (class "Default")
      (node (ref "IC6") (pin "8") (pinfunction "GPB7_8") (pintype "bidirectional"))
      (node (ref "SV1") (pin "16") (pinfunction "16_16") (pintype "passive"))
    )
    (net (code "33") (name "GPB2.0") (class "Default")
      (node (ref "IC7") (pin "1") (pinfunction "GPB0_1") (pintype "bidirectional"))
      (node (ref "SV1") (pin "25") (pinfunction "25_25") (pintype "passive"))
    )
    (net (code "34") (name "GPB2.1") (class "Default")
      (node (ref "IC7") (pin "2") (pinfunction "GPB1_2") (pintype "bidirectional"))
      (node (ref "SV1") (pin "26") (pinfunction "26_26") (pintype "passive"))
    )
    (net (code "35") (name "GPB2.2") (class "Default")
      (node (ref "IC7") (pin "3") (pinfunction "GPB2_3") (pintype "bidirectional"))
      (node (ref "SV1") (pin "27") (pinfunction "27_27") (pintype "passive"))
    )
    (net (code "36") (name "GPB2.3") (class "Default")
      (node (ref "IC7") (pin "4") (pinfunction "GPB3_4") (pintype "bidirectional"))
      (node (ref "SV1") (pin "28") (pinfunction "28_28") (pintype "passive"))
    )
    (net (code "37") (name "GPB2.4") (class "Default")
      (node (ref "IC7") (pin "5") (pinfunction "GPB4_5") (pintype "bidirectional"))
      (node (ref "SV1") (pin "29") (pinfunction "29_29") (pintype "passive"))
    )
    (net (code "38") (name "GPB2.5") (class "Default")
      (node (ref "SV1") (pin "30") (pinfunction "30_30") (pintype "passive"))
    )
    (net (code "39") (name "GPB2.6") (class "Default")
      (node (ref "IC7") (pin "7") (pinfunction "GPB6_7") (pintype "bidirectional"))
      (node (ref "SV1") (pin "31") (pinfunction "31_31") (pintype "passive"))
    )
    (net (code "40") (name "GPB2.7") (class "Default")
      (node (ref "IC7") (pin "8") (pinfunction "GPB7_8") (pintype "bidirectional"))
      (node (ref "SV1") (pin "32") (pinfunction "32_32") (pintype "passive"))
    )
    (net (code "41") (name "GPIO0") (class "Default")
      (node (ref "U$3") (pin "11") (pinfunction "GP17_11") (pintype "bidirectional"))
    )
    (net (code "42") (name "GPIO1") (class "Default")
      (node (ref "IC1") (pin "1") (pinfunction "I1_1") (pintype "input"))
      (node (ref "U$3") (pin "12") (pinfunction "GP18_12") (pintype "bidirectional"))
    )
    (net (code "43") (name "GPIO2") (class "Default")
      (node (ref "IC1") (pin "2") (pinfunction "I2_2") (pintype "input"))
      (node (ref "U$3") (pin "13") (pinfunction "GP27_13") (pintype "bidirectional"))
    )
    (net (code "44") (name "GPIO3") (class "Default")
      (node (ref "IC1") (pin "3") (pinfunction "I3_3") (pintype "input"))
      (node (ref "U$3") (pin "15") (pinfunction "GP22_15") (pintype "bidirectional"))
    )
    (net (code "45") (name "GPIO4") (class "Default")
      (node (ref "IC1") (pin "4") (pinfunction "I4_4") (pintype "input"))
      (node (ref "U$3") (pin "16") (pinfunction "GP23_16") (pintype "bidirectional"))
    )
    (net (code "46") (name "GPIO5") (class "Default")
      (node (ref "IC1") (pin "5") (pinfunction "I5_5") (pintype "input"))
      (node (ref "U$3") (pin "18") (pinfunction "GP24_18") (pintype "bidirectional"))
    )
    (net (code "47") (name "GPIO6") (class "Default")
      (node (ref "IC1") (pin "6") (pinfunction "I6_6") (pintype "input"))
      (node (ref "U$3") (pin "22") (pinfunction "GP25_22") (pintype "bidirectional"))
    )
    (net (code "48") (name "GPIO7") (class "Default")
      (node (ref "IC1") (pin "7") (pinfunction "I7_7") (pintype "input"))
      (node (ref "U$3") (pin "7") (pinfunction "GP4_7") (pintype "bidirectional"))
    )
    (net (code "49") (name "GPIO21") (class "Default")
      (node (ref "IC1") (pin "8") (pinfunction "I8_8") (pintype "input"))
      (node (ref "U$3") (pin "29") (pinfunction "GP5_29") (pintype "bidirectional"))
    )
    (net (code "50") (name "GPIO27") (class "Default")
      (node (ref "R3") (pin "1") (pinfunction "1_1") (pintype "passive"))
      (node (ref "T3") (pin "3") (pinfunction "C_3") (pintype "passive"))
      (node (ref "U$3") (pin "36") (pinfunction "GP16_36") (pintype "bidirectional"))
    )
    (net (code "51") (name "GPPB2.5") (class "Default")
      (node (ref "IC7") (pin "6") (pinfunction "GPB5_6") (pintype "bidirectional"))
    )
    (net (code "52") (name "INT") (class "Default")
      (node (ref "IC3") (pin "21") (pinfunction "RB0/AN12/INT0/LFT0/SDI/SDA_21") (pintype "bidirectional"))
      (node (ref "K1") (pin "4") (pinfunction "DS1_4") (pintype "passive"))
      (node (ref "R7") (pin "1") (pinfunction "1_1") (pintype "passive"))
    )
    (net (code "53") (name "L") (class "Default")
      (node (ref "C7") (pin "2") (pinfunction "2_2") (pintype "passive"))
      (node (ref "D6") (pin "A") (pinfunction "1_A") (pintype "passive"))
      (node (ref "DCDC3") (pin "AC/L") (pinfunction "AC/L_AC/L") (pintype "input"))
      (node (ref "K12") (pin "P") (pinfunction "P_P") (pintype "passive"))
      (node (ref "K12") (pin "P@") (pinfunction "P_P@") (pintype "passive"))
      (node (ref "K13") (pin "3") (pinfunction "PA_3") (pintype "passive"))
      (node (ref "K13") (pin "6") (pinfunction "PB_6") (pintype "passive"))
      (node (ref "K14") (pin "3") (pinfunction "PA_3") (pintype "passive"))
      (node (ref "K14") (pin "6") (pinfunction "PB_6") (pintype "passive"))
      (node (ref "K15") (pin "3") (pinfunction "PA_3") (pintype "passive"))
      (node (ref "K15") (pin "6") (pinfunction "PB_6") (pintype "passive"))
      (node (ref "K16") (pin "P") (pinfunction "P_P") (pintype "passive"))
      (node (ref "K16") (pin "P@") (pinfunction "P_P@") (pintype "passive"))
      (node (ref "K17") (pin "P") (pinfunction "P_P") (pintype "passive"))
      (node (ref "K17") (pin "P@") (pinfunction "P_P@") (pintype "passive"))
      (node (ref "K8") (pin "P") (pinfunction "P_P") (pintype "passive"))
      (node (ref "K8") (pin "P@") (pinfunction "P_P@") (pintype "passive"))
      (node (ref "R19") (pin "1") (pinfunction "1_1") (pintype "passive"))
      (node (ref "R30") (pin "1") (pinfunction "1_1") (pintype "passive"))
      (node (ref "R31") (pin "1") (pinfunction "1_1") (pintype "passive"))
      (node (ref "R32") (pin "1") (pinfunction "1_1") (pintype "passive"))
      (node (ref "R33") (pin "1") (pinfunction "1_1") (pintype "passive"))
      (node (ref "R34") (pin "1") (pinfunction "1_1") (pintype "passive"))
      (node (ref "X1") (pin "1") (pinfunction "KL_1") (pintype "passive"))
    )
    (net (code "54") (name "L-MOTOR") (class "Default")
      (node (ref "F1") (pin "2") (pinfunction "2_2") (pintype "passive"))
      (node (ref "K13") (pin "4") (pinfunction "SA_4") (pintype "passive"))
      (node (ref "K13") (pin "5") (pinfunction "SB_5") (pintype "passive"))
    )
    (net (code "55") (name "MISO") (class "Default")
      (node (ref "IC6") (pin "14") (pinfunction "SO_14") (pintype "output"))
      (node (ref "IC7") (pin "14") (pinfunction "SO_14") (pintype "output"))
      (node (ref "U$3") (pin "21") (pinfunction "GP9_21") (pintype "bidirectional"))
    )
    (net (code "56") (name "MOSI") (class "Default")
      (node (ref "IC6") (pin "13") (pinfunction "SI_13") (pintype "input"))
      (node (ref "IC7") (pin "13") (pinfunction "SI_13") (pintype "input"))
      (node (ref "U$3") (pin "19") (pinfunction "GP10_19") (pintype "bidirectional"))
    )
    (net (code "57") (name "NTC") (class "Default")
      (node (ref "C10") (pin "1") (pinfunction "1_1") (pintype "passive"))
      (node (ref "IC2") (pin "3") (pinfunction "+IN_3") (pintype "input"))
      (node (ref "R8") (pin "1") (pinfunction "1_1") (pintype "passive"))
      (node (ref "X8") (pin "1") (pinfunction "KL_1") (pintype "passive"))
    )
    (net (code "58") (name "N_MOTOR") (class "Default")
      (node (ref "B1") (pin "AC2") (pinfunction "AC2_AC2") (pintype "passive"))
      (node (ref "B2") (pin "AC2") (pinfunction "AC2_AC2") (pintype "passive"))
      (node (ref "D5") (pin "A") (pinfunction "1_A") (pintype "passive"))
      (node (ref "X1") (pin "3") (pinfunction "KL_3") (pintype "passive"))
    )
    (net (code "59") (name "Net-(B1-Pad+)") (class "Default")
      (node (ref "B1") (pin "+") (pinfunction "+_+") (pintype "passive"))
      (node (ref "D2") (pin "A") (pinfunction "A_A") (pintype "passive"))
      (node (ref "R2") (pin "2") (pinfunction "2_2") (pintype "passive"))
    )
    (net (code "60") (name "Net-(B2-PadAC1)") (class "Default")
      (node (ref "B2") (pin "AC1") (pinfunction "AC1_AC1") (pintype "passive"))
      (node (ref "C2") (pin "2") (pinfunction "2_2") (pintype "passive"))
      (node (ref "L1") (pin "2") (pinfunction "2_2") (pintype "passive"))
    )
    (net (code "61") (name "Net-(C1-Pad+)") (class "Default")
      (node (ref "C1") (pin "+") (pinfunction "+_+") (pintype "passive"))
      (node (ref "D2") (pin "C") (pinfunction "C_C") (pintype "passive"))
      (node (ref "R1") (pin "1") (pinfunction "1_1") (pintype "passive"))
    )
    (net (code "62") (name "Net-(C2-Pad1)") (class "Default")
      (node (ref "C2") (pin "1") (pinfunction "1_1") (pintype "passive"))
      (node (ref "R6") (pin "1") (pinfunction "1_1") (pintype "passive"))
    )
    (net (code "63") (name "Net-(C4-Pad2)") (class "Default")
      (node (ref "C4") (pin "2") (pinfunction "2_2") (pintype "passive"))
      (node (ref "R14") (pin "2") (pinfunction "2_2") (pintype "passive"))
    )
    (net (code "64") (name "Net-(D1-PadC)") (class "Default")
      (node (ref "D1") (pin "C") (pinfunction "C_C") (pintype "passive"))
      (node (ref "R2") (pin "1") (pinfunction "1_1") (pintype "passive"))
      (node (ref "R4") (pin "2") (pinfunction "2_2") (pintype "passive"))
    )
    (net (code "65") (name "Net-(D5-2)") (class "Default")
      (node (ref "D5") (pin "C") (pinfunction "2_C") (pintype "passive"))
      (node (ref "L1") (pin "1") (pinfunction "1_1") (pintype "passive"))
      (node (ref "T2") (pin "T1") (pinfunction "A1_T1") (pintype "passive"))
    )
    (net (code "66") (name "Net-(D6-2)") (class "Default")
      (node (ref "C7") (pin "1") (pinfunction "1_1") (pintype "passive"))
      (node (ref "D6") (pin "C") (pinfunction "2_C") (pintype "passive"))
      (node (ref "DCDC3") (pin "AC/N") (pinfunction "AC/N_AC/N") (pintype "input"))
      (node (ref "X1") (pin "2") (pinfunction "KL_2") (pintype "passive"))
    )
    (net (code "67") (name "Net-(IC1-O1)") (class "Default")
      (node (ref "IC1") (pin "18") (pinfunction "O1_18") (pintype "open_collector"))
      (node (ref "K13") (pin "8") (pinfunction "2_8") (pintype "passive"))
      (node (ref "LED2") (pin "C") (pinfunction "C_C") (pintype "passive"))
    )
    (net (code "68") (name "Net-(IC1-O2)") (class "Default")
      (node (ref "IC1") (pin "17") (pinfunction "O2_17") (pintype "open_collector"))
      (node (ref "K14") (pin "8") (pinfunction "2_8") (pintype "passive"))
      (node (ref "LED3") (pin "C") (pinfunction "C_C") (pintype "passive"))
    )
    (net (code "69") (name "Net-(IC1-O3)") (class "Default")
      (node (ref "IC1") (pin "16") (pinfunction "O3_16") (pintype "open_collector"))
      (node (ref "K16") (pin "2") (pinfunction "2_2") (pintype "passive"))
      (node (ref "LED4") (pin "C") (pinfunction "C_C") (pintype "passive"))
    )
    (net (code "70") (name "Net-(IC1-O4)") (class "Default")
      (node (ref "IC1") (pin "15") (pinfunction "O4_15") (pintype "open_collector"))
      (node (ref "K8") (pin "2") (pinfunction "2_2") (pintype "passive"))
      (node (ref "LED8") (pin "C") (pinfunction "C_C") (pintype "passive"))
    )
    (net (code "71") (name "Net-(IC1-O5)") (class "Default")
      (node (ref "IC1") (pin "14") (pinfunction "O5_14") (pintype "open_collector"))
      (node (ref "K12") (pin "2") (pinfunction "2_2") (pintype "passive"))
      (node (ref "LED7") (pin "C") (pinfunction "C_C") (pintype "passive"))
    )
    (net (code "72") (name "Net-(IC1-O6)") (class "Default")
      (node (ref "IC1") (pin "13") (pinfunction "O6_13") (pintype "open_collector"))
      (node (ref "K17") (pin "2") (pinfunction "2_2") (pintype "passive"))
      (node (ref "LED6") (pin "C") (pinfunction "C_C") (pintype "passive"))
    )
    (net (code "73") (name "Net-(IC1-O7)") (class "Default")
      (node (ref "IC1") (pin "12") (pinfunction "O7_12") (pintype "open_collector"))
      (node (ref "K15") (pin "8") (pinfunction "2_8") (pintype "passive"))
      (node (ref "LED5") (pin "C") (pinfunction "C_C") (pintype "passive"))
    )
    (net (code "74") (name "Net-(IC1-O8)") (class "Default")
      (node (ref "IC1") (pin "11") (pinfunction "O8_11") (pintype "open_collector"))
      (node (ref "X6") (pin "3") (pinfunction "KL_3") (pintype "passive"))
    )
    (net (code "75") (name "Net-(IC2A--IN)") (class "Default")
      (node (ref "C6") (pin "1") (pinfunction "1_1") (pintype "passive"))
      (node (ref "IC2") (pin "1") (pinfunction "OUT_1") (pintype "output"))
      (node (ref "IC2") (pin "2") (pinfunction "-IN_2") (pintype "input"))
      (node (ref "IC3") (pin "2") (pinfunction "RA0/AN0_2") (pintype "bidirectional"))
    )
    (net (code "76") (name "Net-(IC2B-+IN)") (class "Default")
      (node (ref "C13") (pin "1") (pinfunction "1_1") (pintype "passive"))
      (node (ref "D10") (pin "C") (pinfunction "C_C") (pintype "passive"))
      (node (ref "IC2") (pin "5") (pinfunction "+IN_5") (pintype "input"))
      (node (ref "R10") (pin "2") (pinfunction "2_2") (pintype "passive"))
      (node (ref "R22") (pin "1") (pinfunction "1_1") (pintype "passive"))
      (node (ref "R23") (pin "2") (pinfunction "2_2") (pintype "passive"))
    )
    (net (code "77") (name "Net-(IC2B--IN)") (class "Default")
      (node (ref "C15") (pin "1") (pinfunction "1_1") (pintype "passive"))
      (node (ref "IC2") (pin "6") (pinfunction "-IN_6") (pintype "input"))
      (node (ref "R20") (pin "2") (pinfunction "2_2") (pintype "passive"))
      (node (ref "R21") (pin "1") (pinfunction "1_1") (pintype "passive"))
    )
    (net (code "78") (name "Net-(IC2B-OUT)") (class "Default")
      (node (ref "IC2") (pin "7") (pinfunction "OUT_7") (pintype "output"))
      (node (ref "IC3") (pin "13") (pinfunction "RC2/CCP1/P1A_13") (pintype "bidirectional"))
      (node (ref "R10") (pin "1") (pinfunction "1_1") (pintype "passive"))
    )
    (net (code "79") (name "Net-(IC3-OSC1{slash}CLKI)") (class "Default")
      (node (ref "C9") (pin "1") (pinfunction "1_1") (pintype "passive"))
      (node (ref "IC3") (pin "9") (pinfunction "OSC1/CLKI_9") (pintype "input"))
      (node (ref "Q2") (pin "2") (pinfunction "2_2") (pintype "passive"))
    )
    (net (code "80") (name "Net-(IC3-RA5{slash}AN4{slash}~{SS}{slash}HLVDIN{slash}C2OUT)") (class "Default")
      (node (ref "IC3") (pin "7") (pinfunction "RA5/AN4/~{SS}/HLVDIN/C2OUT_7") (pintype "bidirectional"))
      (node (ref "R13") (pin "2") (pinfunction "2_2") (pintype "passive"))
    )
    (net (code "81") (name "Net-(IC3-RA6{slash}OSC2{slash}CLKO)") (class "Default")
      (node (ref "C8") (pin "1") (pinfunction "1_1") (pintype "passive"))
      (node (ref "IC3") (pin "10") (pinfunction "RA6/OSC2/CLKO_10") (pintype "output"))
      (node (ref "Q2") (pin "1") (pinfunction "1_1") (pintype "passive"))
    )
    (net (code "82") (name "Net-(IC3-RC1{slash}T1OSI{slash}ICCP2{slash}~{UOE})") (class "Default")
      (node (ref "IC3") (pin "12") (pinfunction "RC1/T1OSI/ICCP2/~{UOE}_12") (pintype "bidirectional"))
      (node (ref "R12") (pin "1") (pinfunction "1_1") (pintype "passive"))
    )
    (net (code "83") (name "Net-(IC4B-I)") (class "Default")
      (node (ref "C11") (pin "1") (pinfunction "1_1") (pintype "passive"))
      (node (ref "IC4") (pin "3") (pinfunction "I_3") (pintype "input"))
      (node (ref "R17") (pin "1") (pinfunction "1_1") (pintype "passive"))
    )
    (net (code "84") (name "Net-(IC4B-O)") (class "Default")
      (node (ref "C12") (pin "1") (pinfunction "1_1") (pintype "passive"))
      (node (ref "IC4") (pin "4") (pinfunction "O_4") (pintype "output"))
      (node (ref "R12") (pin "2") (pinfunction "2_2") (pintype "passive"))
      (node (ref "R16") (pin "1") (pinfunction "1_1") (pintype "passive"))
    )
    (net (code "85") (name "Net-(IC4C-O)") (class "Default")
      (node (ref "IC4") (pin "6") (pinfunction "O_6") (pintype "output"))
      (node (ref "IC5") (pin "2") (pinfunction "I2_2") (pintype "input"))
    )
    (net (code "86") (name "Net-(IC5-O1)") (class "Default")
      (node (ref "IC5") (pin "18") (pinfunction "O1_18") (pintype "open_collector"))
      (node (ref "K6") (pin "8") (pinfunction "2_8") (pintype "passive"))
    )
    (net (code "87") (name "Net-(IC5-O2)") (class "Default")
      (node (ref "IC5") (pin "17") (pinfunction "O2_17") (pintype "open_collector"))
      (node (ref "K7") (pin "8") (pinfunction "2_8") (pintype "passive"))
    )
    (net (code "88") (name "Net-(IC5-O3)") (class "Default")
      (node (ref "IC5") (pin "16") (pinfunction "O3_16") (pintype "open_collector"))
      (node (ref "K9") (pin "8") (pinfunction "2_8") (pintype "passive"))
    )
    (net (code "89") (name "Net-(K1-A)") (class "Default")
      (node (ref "D3") (pin "C") (pinfunction "C_C") (pintype "passive"))
      (node (ref "K1") (pin "1") (pinfunction "A_1") (pintype "passive"))
      (node (ref "R1") (pin "2") (pinfunction "2_2") (pintype "passive"))
    )
    (net (code "90") (name "Net-(K1-K)") (class "Default")
      (node (ref "K1") (pin "2") (pinfunction "K_2") (pintype "passive"))
      (node (ref "T1") (pin "3") (pinfunction "C_3") (pintype "passive"))
    )
    (net (code "91") (name "Net-(K2-DS1)") (class "Default")
      (node (ref "K2") (pin "3") (pinfunction "DS1_3") (pintype "passive"))
      (node (ref "R5") (pin "1") (pinfunction "1_1") (pintype "passive"))
    )
    (net (code "92") (name "Net-(K2-DS2)") (class "Default")
      (node (ref "K2") (pin "4") (pinfunction "DS2_4") (pintype "passive"))
      (node (ref "T2") (pin "G") (pinfunction "G_G") (pintype "passive"))
    )
    (net (code "93") (name "Net-(K6A-OA)") (class "Default")
      (node (ref "K6") (pin "2") (pinfunction "OA_2") (pintype "passive"))
      (node (ref "K6") (pin "7") (pinfunction "OB_7") (pintype "passive"))
      (node (ref "K7") (pin "2") (pinfunction "OA_2") (pintype "passive"))
      (node (ref "K7") (pin "7") (pinfunction "OB_7") (pintype "passive"))
      (node (ref "K9") (pin "3") (pinfunction "PA_3") (pintype "passive"))
      (node (ref "K9") (pin "6") (pinfunction "PB_6") (pintype "passive"))
    )
    (net (code "94") (name "Net-(K6A-PA)") (class "Default")
      (node (ref "D7") (pin "1") (pinfunction "1_1") (pintype "passive"))
      (node (ref "K6") (pin "3") (pinfunction "PA_3") (pintype "passive"))
      (node (ref "K6") (pin "6") (pinfunction "PB_6") (pintype "passive"))
      (node (ref "X5") (pin "2") (pinfunction "KL_2") (pintype "passive"))
    )
    (net (code "95") (name "Net-(K6A-SA)") (class "Default")
      (node (ref "D9") (pin "2") (pinfunction "2_2") (pintype "passive"))
      (node (ref "K6") (pin "4") (pinfunction "SA_4") (pintype "passive"))
      (node (ref "K6") (pin "5") (pinfunction "SB_5") (pintype "passive"))
      (node (ref "K7") (pin "4") (pinfunction "SA_4") (pintype "passive"))
      (node (ref "K7") (pin "5") (pinfunction "SB_5") (pintype "passive"))
      (node (ref "X4") (pin "1") (pinfunction "KL_1") (pintype "passive"))
    )
    (net (code "96") (name "Net-(K7A-PA)") (class "Default")
      (node (ref "B2") (pin "-") (pinfunction "-_-") (pintype "passive"))
      (node (ref "K7") (pin "3") (pinfunction "PA_3") (pintype "passive"))
      (node (ref "K7") (pin "6") (pinfunction "PB_6") (pintype "passive"))
      (node (ref "R15") (pin "1") (pinfunction "1_1") (pintype "passive"))
    )
    (net (code "97") (name "Net-(K9A-OA)") (class "Default")
      (node (ref "D9") (pin "1") (pinfunction "1_1") (pintype "passive"))
      (node (ref "K9") (pin "2") (pinfunction "OA_2") (pintype "passive"))
      (node (ref "K9") (pin "7") (pinfunction "OB_7") (pintype "passive"))
      (node (ref "X4") (pin "3") (pinfunction "KL_3") (pintype "passive"))
    )
    (net (code "98") (name "Net-(K9A-SA)") (class "Default")
      (node (ref "K9") (pin "4") (pinfunction "SA_4") (pintype "passive"))
      (node (ref "K9") (pin "5") (pinfunction "SB_5") (pintype "passive"))
      (node (ref "X4") (pin "2") (pinfunction "KL_2") (pintype "passive"))
    )
    (net (code "99") (name "Net-(K14A-SA)") (class "Default")
      (node (ref "K14") (pin "4") (pinfunction "SA_4") (pintype "passive"))
      (node (ref "K14") (pin "5") (pinfunction "SB_5") (pintype "passive"))
      (node (ref "R19") (pin "2") (pinfunction "2_2") (pintype "passive"))
      (node (ref "X2") (pin "1") (pinfunction "KL_1") (pintype "passive"))
    )
    (net (code "100") (name "Net-(K15A-SA)") (class "Default")
      (node (ref "K15") (pin "4") (pinfunction "SA_4") (pintype "passive"))
      (node (ref "K15") (pin "5") (pinfunction "SB_5") (pintype "passive"))
      (node (ref "R34") (pin "2") (pinfunction "2_2") (pintype "passive"))
      (node (ref "X2") (pin "4") (pinfunction "KL_4") (pintype "passive"))
    )
    (net (code "101") (name "Net-(LED1-PadA)") (class "Default")
      (node (ref "LED1") (pin "A") (pinfunction "A_A") (pintype "passive"))
      (node (ref "R13") (pin "1") (pinfunction "1_1") (pintype "passive"))
    )
    (net (code "102") (name "Net-(LED2-PadA)") (class "Default")
      (node (ref "LED2") (pin "A") (pinfunction "A_A") (pintype "passive"))
      (node (ref "R11") (pin "1") (pinfunction "1_1") (pintype "passive"))
    )
    (net (code "103") (name "Net-(LED3-PadA)") (class "Default")
      (node (ref "LED3") (pin "A") (pinfunction "A_A") (pintype "passive"))
      (node (ref "R24") (pin "1") (pinfunction "1_1") (pintype "passive"))
    )
    (net (code "104") (name "Net-(LED4-PadA)") (class "Default")
      (node (ref "LED4") (pin "A") (pinfunction "A_A") (pintype "passive"))
      (node (ref "R25") (pin "1") (pinfunction "1_1") (pintype "passive"))
    )
    (net (code "105") (name "Net-(LED5-PadA)") (class "Default")
      (node (ref "LED5") (pin "A") (pinfunction "A_A") (pintype "passive"))
      (node (ref "R26") (pin "1") (pinfunction "1_1") (pintype "passive"))
    )
    (net (code "106") (name "Net-(LED6-PadA)") (class "Default")
      (node (ref "LED6") (pin "A") (pinfunction "A_A") (pintype "passive"))
      (node (ref "R27") (pin "1") (pinfunction "1_1") (pintype "passive"))
    )
    (net (code "107") (name "Net-(LED7-PadA)") (class "Default")
      (node (ref "LED7") (pin "A") (pinfunction "A_A") (pintype "passive"))
      (node (ref "R28") (pin "1") (pinfunction "1_1") (pintype "passive"))
    )
    (net (code "108") (name "Net-(LED8-PadA)") (class "Default")
      (node (ref "LED8") (pin "A") (pinfunction "A_A") (pintype "passive"))
      (node (ref "R29") (pin "1") (pinfunction "1_1") (pintype "passive"))
    )
    (net (code "109") (name "Net-(R14-Pad1)") (class "Default")
      (node (ref "R14") (pin "1") (pinfunction "1_1") (pintype "passive"))
      (node (ref "R15") (pin "2") (pinfunction "2_2") (pintype "passive"))
    )
    (net (code "110") (name "Net-(T1-B)") (class "Default")
      (node (ref "R4") (pin "1") (pinfunction "1_1") (pintype "passive"))
      (node (ref "R9") (pin "2") (pinfunction "2_2") (pintype "passive"))
      (node (ref "T1") (pin "2") (pinfunction "B_2") (pintype "passive"))
    )
    (net (code "111") (name "Net-(T1-E)") (class "Default")
      (node (ref "B1") (pin "-") (pinfunction "-_-") (pintype "passive"))
      (node (ref "C1") (pin "-") (pinfunction "-_-") (pintype "passive"))
      (node (ref "D1") (pin "A") (pinfunction "A_A") (pintype "passive"))
      (node (ref "D3") (pin "A") (pinfunction "A_A") (pintype "passive"))
      (node (ref "R9") (pin "1") (pinfunction "1_1") (pintype "passive"))
      (node (ref "T1") (pin "1") (pinfunction "E_1") (pintype "passive"))
    )
    (net (code "112") (name "Net-(T2-A2)") (class "Default")
      (node (ref "B1") (pin "AC1") (pinfunction "AC1_AC1") (pintype "passive"))
      (node (ref "F1") (pin "1") (pinfunction "1_1") (pintype "passive"))
      (node (ref "R5") (pin "2") (pinfunction "2_2") (pintype "passive"))
      (node (ref "R6") (pin "2") (pinfunction "2_2") (pintype "passive"))
      (node (ref "T2") (pin "T2") (pinfunction "A2_T2") (pintype "passive"))
    )
    (net (code "113") (name "Net-(T3-B)") (class "Default")
      (node (ref "R18") (pin "2") (pinfunction "2_2") (pintype "passive"))
      (node (ref "T3") (pin "2") (pinfunction "B_2") (pintype "passive"))
      (node (ref "X6") (pin "1") (pinfunction "KL_1") (pintype "passive"))
    )
    (net (code "114") (name "Net-(U$3-GP6)") (class "Default")
      (node (ref "U$3") (pin "31") (pinfunction "GP6_31") (pintype "bidirectional"))
      (node (ref "X6") (pin "4") (pinfunction "KL_4") (pintype "passive"))
    )
    (net (code "115") (name "Net-(U$3-GP19)") (class "Default")
      (node (ref "U$3") (pin "35") (pinfunction "GP19_35") (pintype "bidirectional"))
      (node (ref "X6") (pin "5") (pinfunction "KL_5") (pintype "passive"))
    )
    (net (code "116") (name "Net-(U$3-GP26)") (class "Default")
      (node (ref "U$3") (pin "37") (pinfunction "GP26_37") (pintype "bidirectional"))
      (node (ref "X6") (pin "6") (pinfunction "KL_6") (pintype "passive"))
    )
    (net (code "117") (name "Net-(X2B-KL)") (class "Default")
      (node (ref "K16") (pin "S") (pinfunction "S_S") (pintype "passive"))
      (node (ref "R30") (pin "2") (pinfunction "2_2") (pintype "passive"))
      (node (ref "X2") (pin "2") (pinfunction "KL_2") (pintype "passive"))
    )
    (net (code "118") (name "Net-(X2C-KL)") (class "Default")
      (node (ref "K8") (pin "S") (pinfunction "S_S") (pintype "passive"))
      (node (ref "R31") (pin "2") (pinfunction "2_2") (pintype "passive"))
      (node (ref "X2") (pin "3") (pinfunction "KL_3") (pintype "passive"))
    )
    (net (code "119") (name "Net-(X2E-KL)") (class "Default")
      (node (ref "K17") (pin "S") (pinfunction "S_S") (pintype "passive"))
      (node (ref "R32") (pin "2") (pinfunction "2_2") (pintype "passive"))
      (node (ref "X2") (pin "5") (pinfunction "KL_5") (pintype "passive"))
    )
    (net (code "120") (name "Net-(X2F-KL)") (class "Default")
      (node (ref "K12") (pin "S") (pinfunction "S_S") (pintype "passive"))
      (node (ref "R33") (pin "2") (pinfunction "2_2") (pintype "passive"))
      (node (ref "X2") (pin "6") (pinfunction "KL_6") (pintype "passive"))
    )
    (net (code "121") (name "Net-(X3A-KL)") (class "Default")
      (node (ref "R16") (pin "2") (pinfunction "2_2") (pintype "passive"))
      (node (ref "X3") (pin "1") (pinfunction "KL_1") (pintype "passive"))
    )
    (net (code "122") (name "Net-(X3B-KL)") (class "Default")
      (node (ref "R17") (pin "2") (pinfunction "2_2") (pintype "passive"))
      (node (ref "X3") (pin "2") (pinfunction "KL_2") (pintype "passive"))
    )
    (net (code "123") (name "Net-(X5A-KL)") (class "Default")
      (node (ref "B2") (pin "+") (pinfunction "+_+") (pintype "passive"))
      (node (ref "C4") (pin "1") (pinfunction "1_1") (pintype "passive"))
      (node (ref "D7") (pin "2") (pinfunction "2_2") (pintype "passive"))
      (node (ref "X5") (pin "1") (pinfunction "KL_1") (pintype "passive"))
    )
    (net (code "124") (name "PGC") (class "Default")
      (node (ref "IC3") (pin "27") (pinfunction "RB6/KBI2/PGC_27") (pintype "bidirectional"))
      (node (ref "JP1") (pin "5") (pinfunction "5_5") (pintype "passive"))
    )
    (net (code "125") (name "PGD") (class "Default")
      (node (ref "IC3") (pin "28") (pinfunction "RB7/BKI3/PGD_28") (pintype "bidirectional"))
      (node (ref "JP1") (pin "4") (pinfunction "4_4") (pintype "passive"))
    )
    (net (code "126") (name "PGM") (class "Default")
      (node (ref "IC3") (pin "26") (pinfunction "RB5/KBI1/PGM_26") (pintype "bidirectional"))
      (node (ref "JP1") (pin "6") (pinfunction "6_6") (pintype "passive"))
    )
    (net (code "127") (name "PWM0") (class "Default")
      (node (ref "SV1") (pin "33") (pinfunction "33_33") (pintype "passive"))
      (node (ref "U$3") (pin "32") (pinfunction "GP12_32") (pintype "bidirectional"))
    )
    (net (code "128") (name "PWM1") (class "Default")
      (node (ref "SV1") (pin "34") (pinfunction "34_34") (pintype "passive"))
      (node (ref "U$3") (pin "33") (pinfunction "GP13_33") (pintype "bidirectional"))
    )
    (net (code "129") (name "RX") (class "Default")
      (node (ref "IC3") (pin "18") (pinfunction "RC7/RX/DT/SDO_18") (pintype "bidirectional"))
      (node (ref "U$3") (pin "8") (pinfunction "GP14_8") (pintype "bidirectional"))
    )
    (net (code "130") (name "SCK") (class "Default")
      (node (ref "IC6") (pin "12") (pinfunction "SCK_12") (pintype "input"))
      (node (ref "IC7") (pin "12") (pinfunction "SCK_12") (pintype "input"))
      (node (ref "U$3") (pin "23") (pinfunction "GP11_23") (pintype "bidirectional"))
    )
    (net (code "131") (name "SCL") (class "Default")
      (node (ref "U$3") (pin "5") (pinfunction "GP3_5") (pintype "bidirectional"))
      (node (ref "X8") (pin "8") (pinfunction "KL_8") (pintype "passive"))
    )
    (net (code "132") (name "SDA") (class "Default")
      (node (ref "U$3") (pin "3") (pinfunction "GP2_3") (pintype "bidirectional"))
      (node (ref "X8") (pin "7") (pinfunction "KL_7") (pintype "passive"))
    )
    (net (code "133") (name "TACHO") (class "Default")
      (node (ref "C14") (pin "1") (pinfunction "1_1") (pintype "passive"))
      (node (ref "R22") (pin "2") (pinfunction "2_2") (pintype "passive"))
      (node (ref "X8") (pin "3") (pinfunction "KL_3") (pintype "passive"))
    )
    (net (code "134") (name "TRIAC") (class "Default")
      (node (ref "IC3") (pin "6") (pinfunction "RA4/T0CKI/CIOUT/RCV_6") (pintype "bidirectional"))
      (node (ref "K2") (pin "1") (pinfunction "K_1") (pintype "passive"))
    )
    (net (code "135") (name "TX") (class "Default")
      (node (ref "IC3") (pin "17") (pinfunction "RC6/TX/CK_17") (pintype "bidirectional"))
      (node (ref "U$3") (pin "10") (pinfunction "GP15_10") (pintype "bidirectional"))
    )
    (net (code "136") (name "VPP") (class "Default")
      (node (ref "IC3") (pin "1") (pinfunction "~{MCLR}/VPP/RE3_1") (pintype "input"))
      (node (ref "JP1") (pin "1") (pinfunction "1_1") (pintype "passive"))
    )
    (net (code "137") (name "unconnected-(IC3-RA1{slash}AN1-Pad3)") (class "Default")
      (node (ref "IC3") (pin "3") (pinfunction "RA1/AN1_3") (pintype "bidirectional"))
    )
    (net (code "138") (name "unconnected-(IC3-RB1{slash}AN10{slash}INT1{slash}SCK{slash}SCL-Pad22)") (class "Default")
      (node (ref "IC3") (pin "22") (pinfunction "RB1/AN10/INT1/SCK/SCL_22") (pintype "bidirectional"))
    )
    (net (code "139") (name "unconnected-(IC3-RB2{slash}AN8{slash}INT2{slash}VMO-Pad23)") (class "Default")
      (node (ref "IC3") (pin "23") (pinfunction "RB2/AN8/INT2/VMO_23") (pintype "bidirectional"))
    )
    (net (code "140") (name "unconnected-(IC3-RB3{slash}AN9{slash}CCP2{slash}VPO-Pad24)") (class "Default")
      (node (ref "IC3") (pin "24") (pinfunction "RB3/AN9/CCP2/VPO_24") (pintype "bidirectional"))
    )
    (net (code "141") (name "unconnected-(IC3-RB4{slash}AN11{slash}KBI0{slash}CSSPP-Pad25)") (class "Default")
      (node (ref "IC3") (pin "25") (pinfunction "RB4/AN11/KBI0/CSSPP_25") (pintype "bidirectional"))
    )
    (net (code "142") (name "unconnected-(IC3-RC0{slash}TIOSO{slash}T13CKI-Pad11)") (class "Default")
      (node (ref "IC3") (pin "11") (pinfunction "RC0/TIOSO/T13CKI_11") (pintype "bidirectional"))
    )
    (net (code "143") (name "unconnected-(IC3-RC4{slash}D-{slash}VM-Pad15)") (class "Default")
      (node (ref "IC3") (pin "15") (pinfunction "RC4/D-/VM_15") (pintype "bidirectional"))
    )
    (net (code "144") (name "unconnected-(IC3-RC5{slash}D+{slash}VP-Pad16)") (class "Default")
      (node (ref "IC3") (pin "16") (pinfunction "RC5/D+/VP_16") (pintype "bidirectional"))
    )
    (net (code "145") (name "unconnected-(IC3-VUSB-Pad14)") (class "Default")
      (node (ref "IC3") (pin "14") (pinfunction "VUSB_14") (pintype "bidirectional"))
    )
    (net (code "146") (name "unconnected-(IC4A-O-Pad2)") (class "Default")
      (node (ref "IC4") (pin "2") (pinfunction "O_2") (pintype "output"))
    )
    (net (code "147") (name "unconnected-(IC4D-O-Pad8)") (class "Default")
      (node (ref "IC4") (pin "8") (pinfunction "O_8") (pintype "output"))
    )
    (net (code "148") (name "unconnected-(IC4E-O-Pad10)") (class "Default")
      (node (ref "IC4") (pin "10") (pinfunction "O_10") (pintype "output"))
    )
    (net (code "149") (name "unconnected-(IC4F-O-Pad12)") (class "Default")
      (node (ref "IC4") (pin "12") (pinfunction "O_12") (pintype "output"))
    )
    (net (code "150") (name "unconnected-(IC5-O4-Pad15)") (class "Default")
      (node (ref "IC5") (pin "15") (pinfunction "O4_15") (pintype "open_collector"))
    )
    (net (code "151") (name "unconnected-(IC5-O5-Pad14)") (class "Default")
      (node (ref "IC5") (pin "14") (pinfunction "O5_14") (pintype "open_collector"))
    )
    (net (code "152") (name "unconnected-(IC5-O6-Pad13)") (class "Default")
      (node (ref "IC5") (pin "13") (pinfunction "O6_13") (pintype "open_collector"))
    )
    (net (code "153") (name "unconnected-(IC5-O7-Pad12)") (class "Default")
      (node (ref "IC5") (pin "12") (pinfunction "O7_12") (pintype "open_collector"))
    )
    (net (code "154") (name "unconnected-(IC5-O8-Pad11)") (class "Default")
      (node (ref "IC5") (pin "11") (pinfunction "O8_11") (pintype "open_collector"))
    )
    (net (code "155") (name "unconnected-(IC6-INTA-Pad20)") (class "Default")
      (node (ref "IC6") (pin "20") (pinfunction "INTA_20") (pintype "output"))
    )
    (net (code "156") (name "unconnected-(IC6-INTB-Pad19)") (class "Default")
      (node (ref "IC6") (pin "19") (pinfunction "INTB_19") (pintype "output"))
    )
    (net (code "157") (name "unconnected-(IC7-INTA-Pad20)") (class "Default")
      (node (ref "IC7") (pin "20") (pinfunction "INTA_20") (pintype "output"))
    )
    (net (code "158") (name "unconnected-(IC7-INTB-Pad19)") (class "Default")
      (node (ref "IC7") (pin "19") (pinfunction "INTB_19") (pintype "output"))
    )
    (net (code "159") (name "unconnected-(K8-PadO)") (class "Default")
      (node (ref "K8") (pin "O") (pinfunction "O_O") (pintype "passive"))
    )
    (net (code "160") (name "unconnected-(K12-PadO)") (class "Default")
      (node (ref "K12") (pin "O") (pinfunction "O_O") (pintype "passive"))
    )
    (net (code "161") (name "unconnected-(K13A-OA-Pad2)") (class "Default")
      (node (ref "K13") (pin "2") (pinfunction "OA_2") (pintype "passive"))
    )
    (net (code "162") (name "unconnected-(K13A-OB-Pad7)") (class "Default")
      (node (ref "K13") (pin "7") (pinfunction "OB_7") (pintype "passive"))
    )
    (net (code "163") (name "unconnected-(K14A-OA-Pad2)") (class "Default")
      (node (ref "K14") (pin "2") (pinfunction "OA_2") (pintype "passive"))
    )
    (net (code "164") (name "unconnected-(K14A-OB-Pad7)") (class "Default")
      (node (ref "K14") (pin "7") (pinfunction "OB_7") (pintype "passive"))
    )
    (net (code "165") (name "unconnected-(K15A-OA-Pad2)") (class "Default")
      (node (ref "K15") (pin "2") (pinfunction "OA_2") (pintype "passive"))
    )
    (net (code "166") (name "unconnected-(K15A-OB-Pad7)") (class "Default")
      (node (ref "K15") (pin "7") (pinfunction "OB_7") (pintype "passive"))
    )
    (net (code "167") (name "unconnected-(K16-PadO)") (class "Default")
      (node (ref "K16") (pin "O") (pinfunction "O_O") (pintype "passive"))
    )
    (net (code "168") (name "unconnected-(K17-PadO)") (class "Default")
      (node (ref "K17") (pin "O") (pinfunction "O_O") (pintype "passive"))
    )
    (net (code "169") (name "unconnected-(SINK1-1-PadP$1)") (class "Default")
      (node (ref "SINK1") (pin "P$1") (pinfunction "1_P$1") (pintype "bidirectional"))
    )
    (net (code "170") (name "unconnected-(SINK1-2-PadP$2)") (class "Default")
      (node (ref "SINK1") (pin "P$2") (pinfunction "2_P$2") (pintype "bidirectional"))
    )
    (net (code "171") (name "unconnected-(U$3-3V3-Pad1)") (class "Default")
      (node (ref "U$3") (pin "1") (pinfunction "3V3_1") (pintype "bidirectional"))
    )
    (net (code "172") (name "unconnected-(U$3-3V3-Pad17)") (class "Default")
      (node (ref "U$3") (pin "17") (pinfunction "3V3_17") (pintype "bidirectional"))
    )
    (net (code "173") (name "unconnected-(U$3-GP20-Pad38)") (class "Default")
      (node (ref "U$3") (pin "38") (pinfunction "GP20_38") (pintype "bidirectional"))
    )
    (net (code "174") (name "unconnected-(U$3-GP21-Pad40)") (class "Default")
      (node (ref "U$3") (pin "40") (pinfunction "GP21_40") (pintype "bidirectional"))
    )
    (net (code "175") (name "unconnected-(U$3-ID_SC-Pad28)") (class "Default")
      (node (ref "U$3") (pin "28") (pinfunction "ID_SC_28") (pintype "bidirectional"))
    )
    (net (code "176") (name "unconnected-(U$3-ID_SD-Pad27)") (class "Default")
      (node (ref "U$3") (pin "27") (pinfunction "ID_SD_27") (pintype "bidirectional"))
    )
  )
)
